# LoraGateway.net
KiCad netlist of a schematic drawn in EAGLE
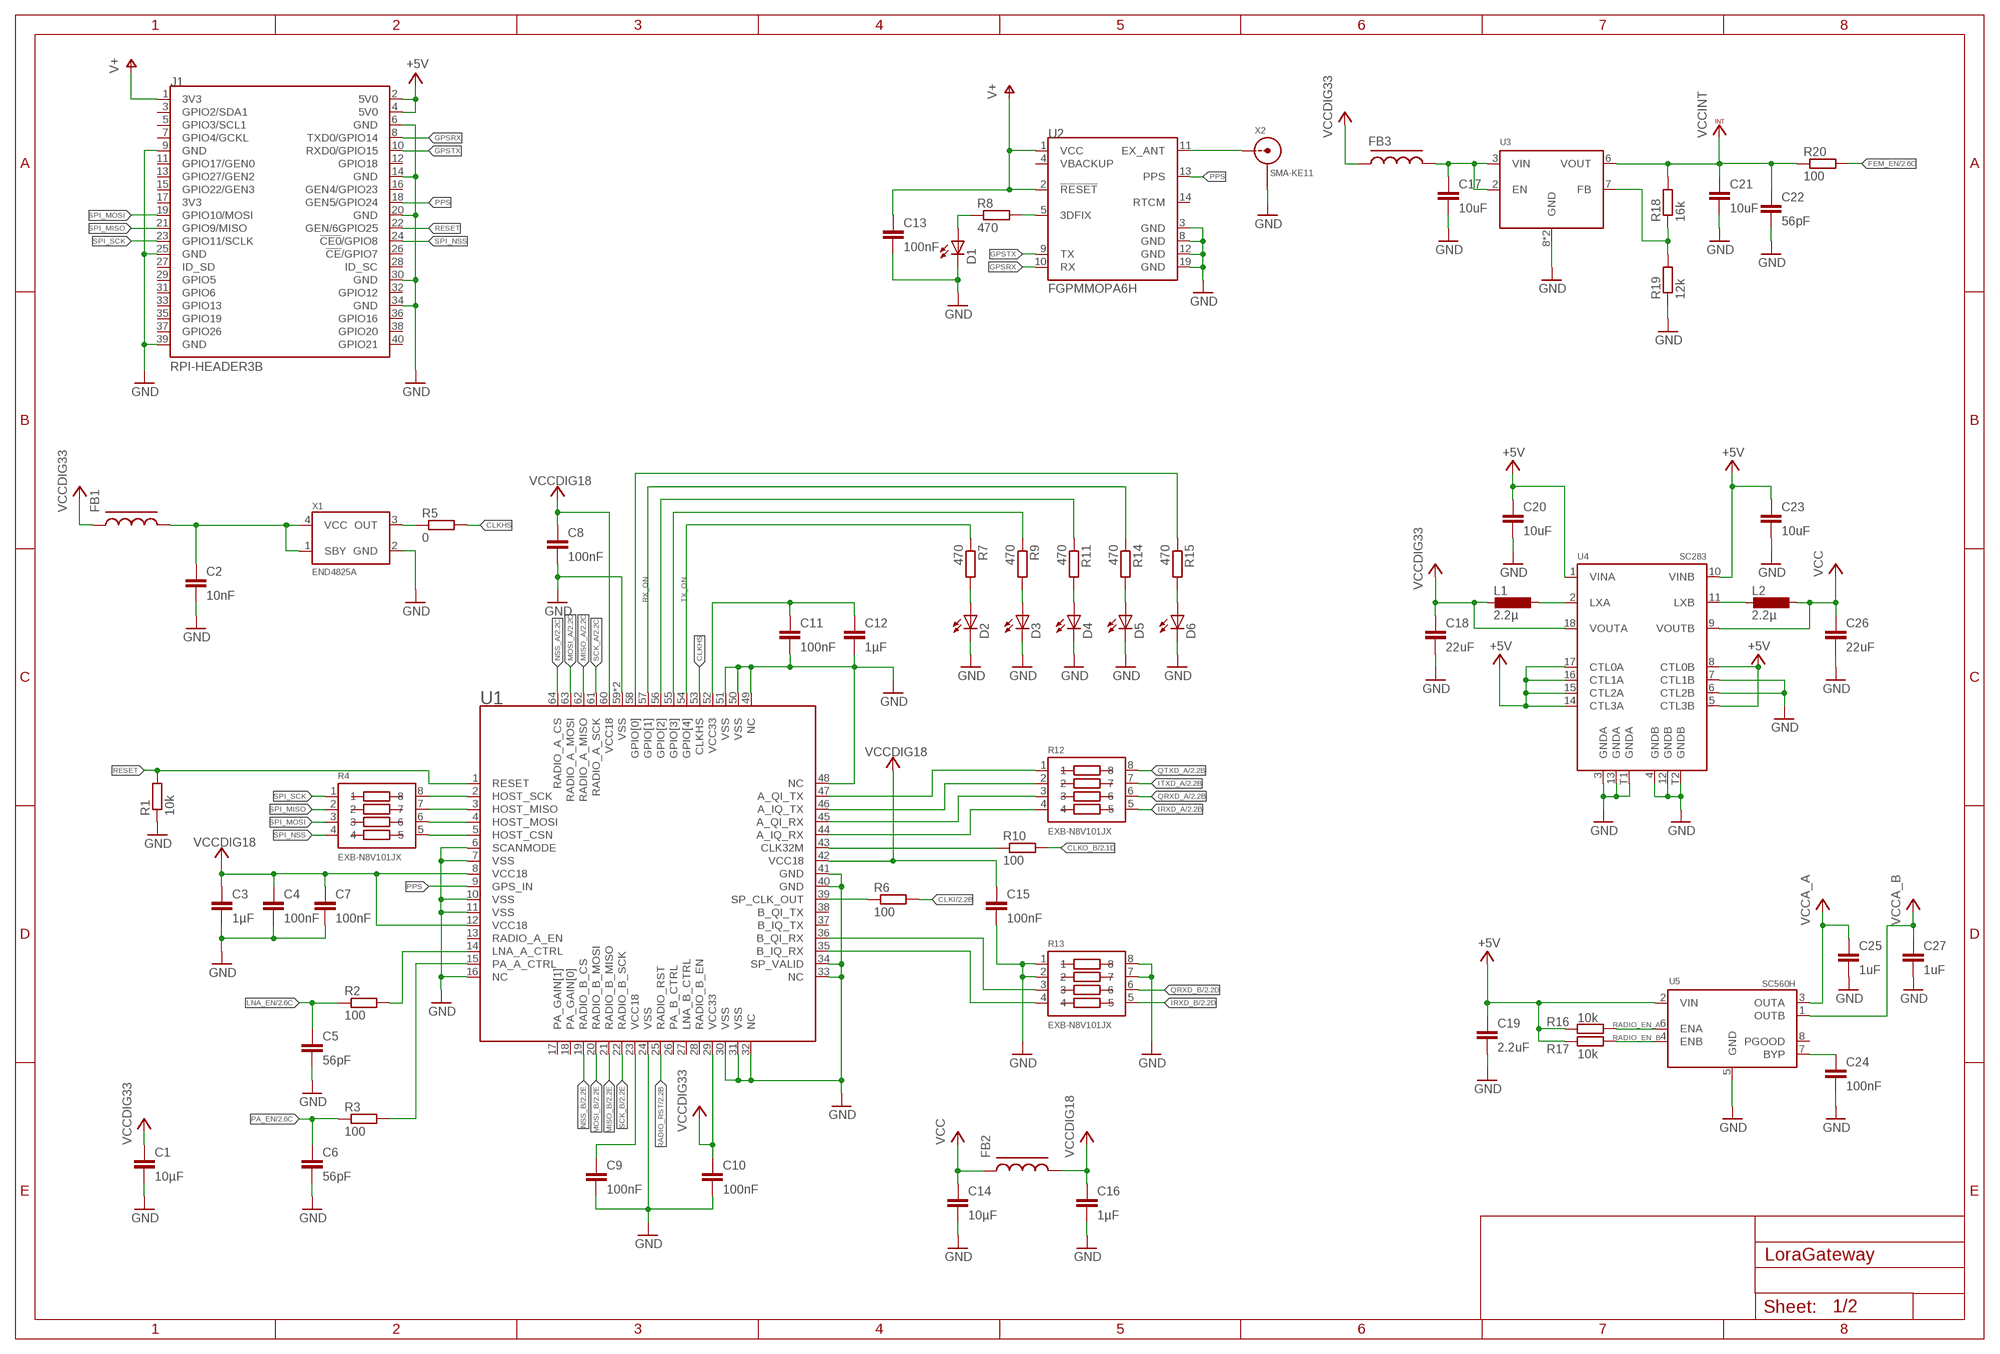
[diagram p0: schematic, sheet 1]
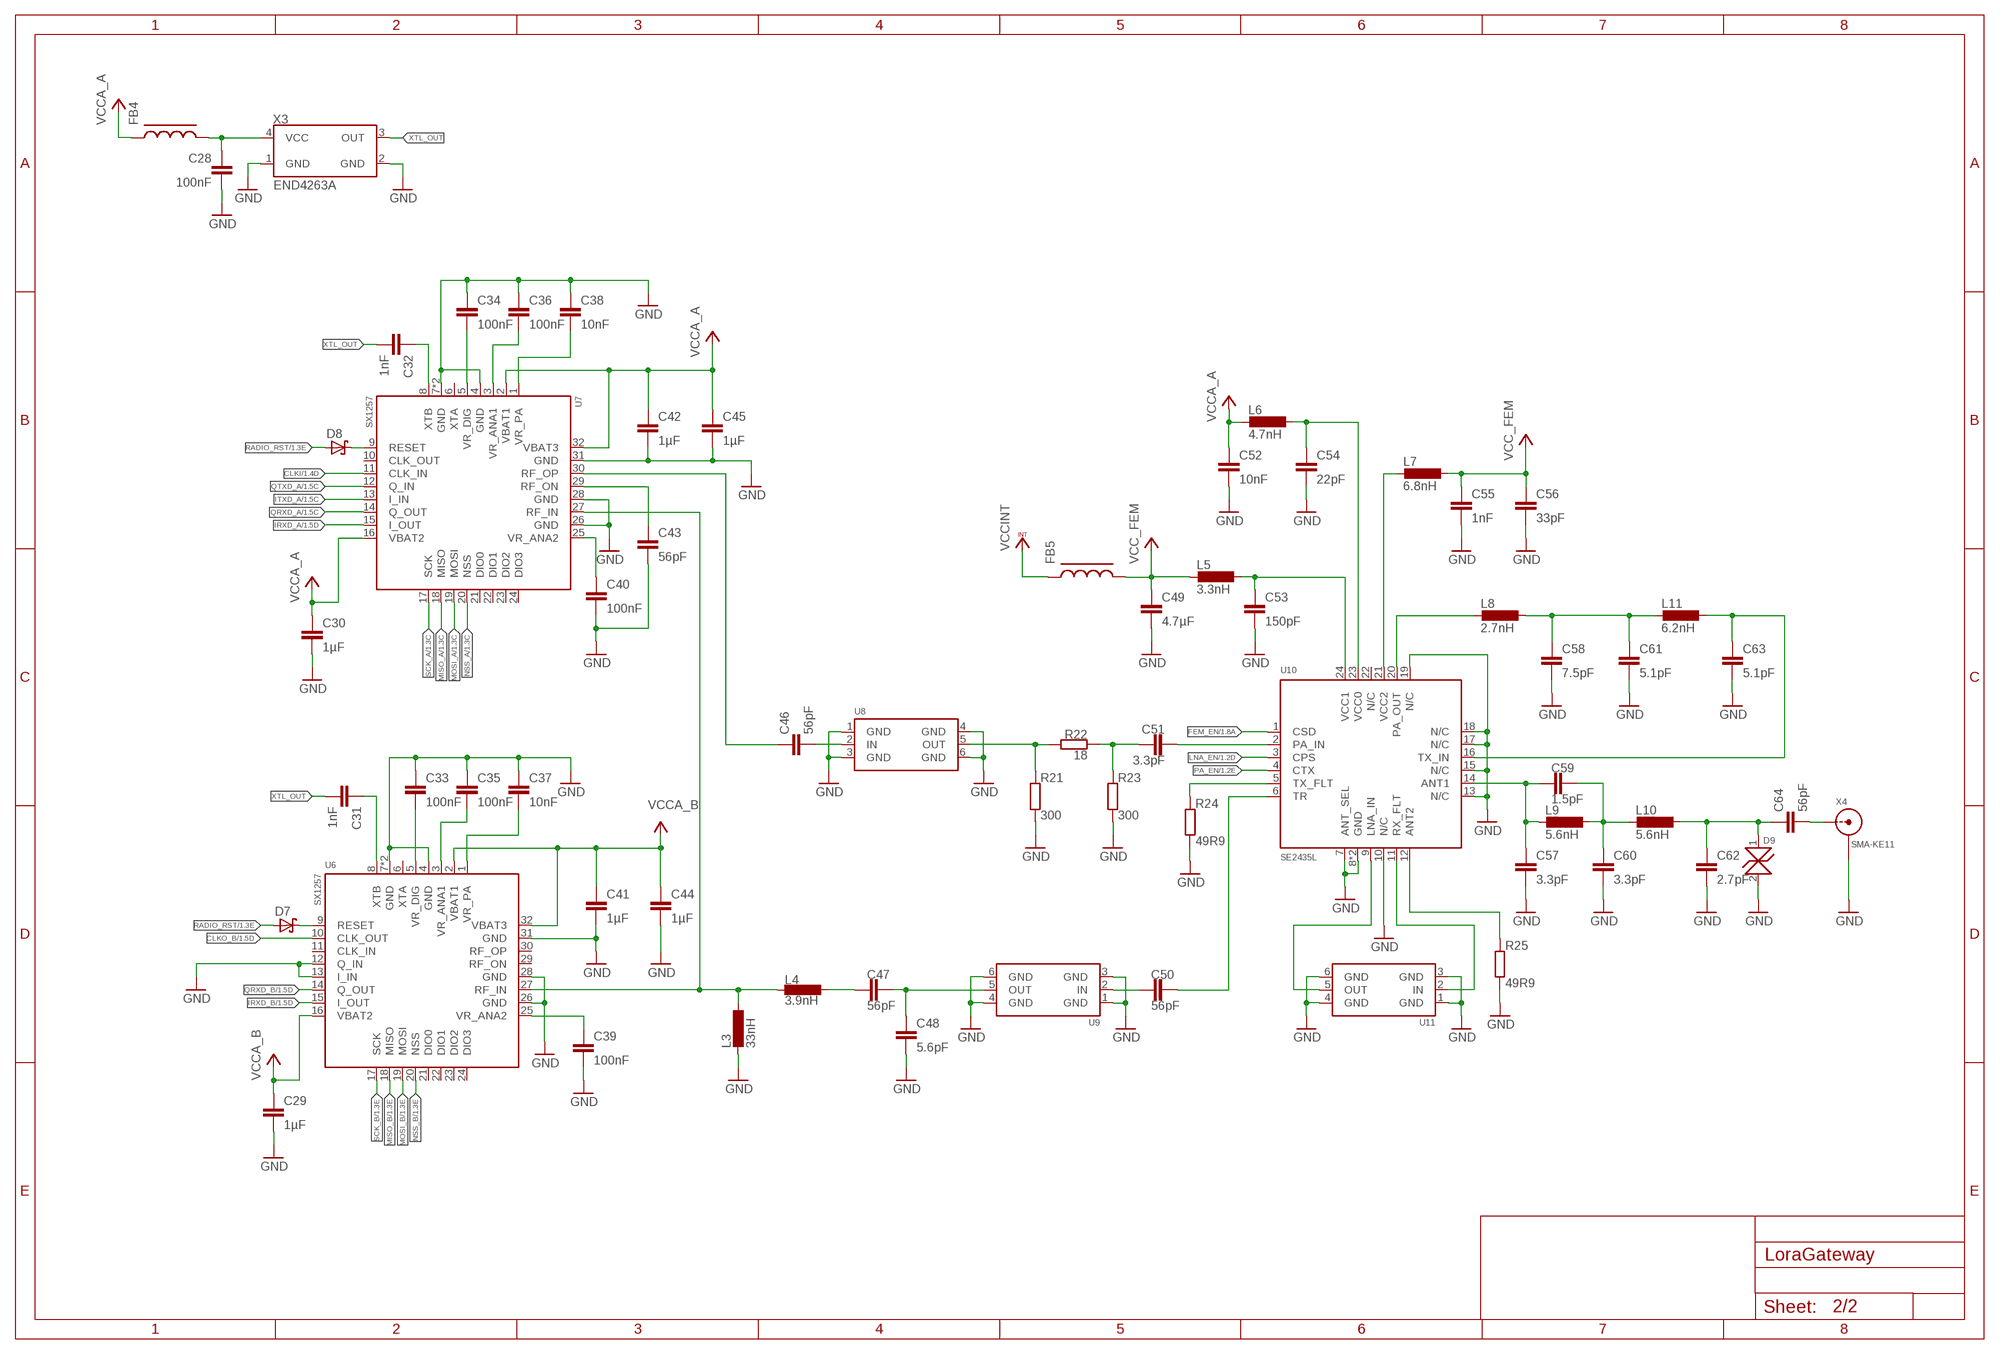
[diagram p1: schematic, sheet 2]

(export (version "E")
  (design (tool "Eeschema 10.0.6"))
  (components
    (comp (ref "C28")
      (value "100nF")
      (footprint "eagle-import:C0402")
      (libsource (lib "eagle-import") (part "C-EU0402"))
    )
    (comp (ref "C29")
      (value "1µF")
      (footprint "eagle-import:C0402")
      (libsource (lib "eagle-import") (part "C-EU0402"))
    )
    (comp (ref "C30")
      (value "1µF")
      (footprint "eagle-import:C0402")
      (libsource (lib "eagle-import") (part "C-EU0402"))
    )
    (comp (ref "C31")
      (value "1nF")
      (footprint "eagle-import:C0402")
      (libsource (lib "eagle-import") (part "C-EU0402"))
    )
    (comp (ref "C32")
      (value "1nF")
      (footprint "eagle-import:C0402")
      (fields (field (name "OC_DIGIKEY") "490-6348-1-ND"))
      (libsource (lib "eagle-import") (part "C-EU0402"))
    )
    (comp (ref "C33")
      (value "100nF")
      (footprint "eagle-import:C0402")
      (libsource (lib "eagle-import") (part "C-EU0402"))
    )
    (comp (ref "C34")
      (value "100nF")
      (footprint "eagle-import:C0402")
      (libsource (lib "eagle-import") (part "C-EU0402"))
    )
    (comp (ref "C35")
      (value "100nF")
      (footprint "eagle-import:C0402")
      (libsource (lib "eagle-import") (part "C-EU0402"))
    )
    (comp (ref "C36")
      (value "100nF")
      (footprint "eagle-import:C0402")
      (libsource (lib "eagle-import") (part "C-EU0402"))
    )
    (comp (ref "C37")
      (value "10nF")
      (footprint "eagle-import:C0402")
      (libsource (lib "eagle-import") (part "C-EU0402"))
    )
    (comp (ref "C38")
      (value "10nF")
      (footprint "eagle-import:C0402")
      (libsource (lib "eagle-import") (part "C-EU0402"))
    )
    (comp (ref "C39")
      (value "100nF")
      (footprint "eagle-import:C0402")
      (libsource (lib "eagle-import") (part "C-EU0402"))
    )
    (comp (ref "C40")
      (value "100nF")
      (footprint "eagle-import:C0402")
      (libsource (lib "eagle-import") (part "C-EU0402"))
    )
    (comp (ref "C41")
      (value "1µF")
      (footprint "eagle-import:C0402")
      (libsource (lib "eagle-import") (part "C-EU0402"))
    )
    (comp (ref "C42")
      (value "1µF")
      (footprint "eagle-import:C0402")
      (libsource (lib "eagle-import") (part "C-EU0402"))
    )
    (comp (ref "C43")
      (value "56pF")
      (footprint "eagle-import:C0402")
      (libsource (lib "eagle-import") (part "C-EU0402"))
    )
    (comp (ref "C44")
      (value "1µF")
      (footprint "eagle-import:C0402")
      (libsource (lib "eagle-import") (part "C-EU0402"))
    )
    (comp (ref "C45")
      (value "1µF")
      (footprint "eagle-import:C0402")
      (libsource (lib "eagle-import") (part "C-EU0402"))
    )
    (comp (ref "C46")
      (value "56pF")
      (footprint "eagle-import:C0402")
      (libsource (lib "eagle-import") (part "C-EU0402"))
    )
    (comp (ref "C47")
      (value "56pF")
      (footprint "eagle-import:C0402")
      (libsource (lib "eagle-import") (part "C-EU0402"))
    )
    (comp (ref "C48")
      (value "5.6pF")
      (footprint "eagle-import:C0402")
      (libsource (lib "eagle-import") (part "C-EU0402"))
    )
    (comp (ref "C49")
      (value "4.7µF")
      (footprint "eagle-import:C0603")
      (libsource (lib "eagle-import") (part "C-EU0603"))
    )
    (comp (ref "C50")
      (value "56pF")
      (footprint "eagle-import:C0402")
      (libsource (lib "eagle-import") (part "C-EU0402"))
    )
    (comp (ref "C51")
      (value "3.3pF")
      (footprint "eagle-import:C0402")
      (libsource (lib "eagle-import") (part "C-EU0402"))
    )
    (comp (ref "C52")
      (value "10nF")
      (footprint "eagle-import:C0402")
      (libsource (lib "eagle-import") (part "C-EU0402"))
    )
    (comp (ref "C53")
      (value "150pF")
      (footprint "eagle-import:C0402")
      (libsource (lib "eagle-import") (part "C-EU0402"))
    )
    (comp (ref "C54")
      (value "22pF")
      (footprint "eagle-import:C0402")
      (libsource (lib "eagle-import") (part "C-EU0402"))
    )
    (comp (ref "C55")
      (value "1nF")
      (footprint "eagle-import:C0402")
      (libsource (lib "eagle-import") (part "C-EU0402"))
    )
    (comp (ref "C56")
      (value "33pF")
      (footprint "eagle-import:C0402")
      (libsource (lib "eagle-import") (part "C-EU0402"))
    )
    (comp (ref "C57")
      (value "3.3pF")
      (footprint "eagle-import:C0402")
      (libsource (lib "eagle-import") (part "C-EU0402"))
    )
    (comp (ref "C58")
      (value "7.5pF")
      (footprint "eagle-import:C0402")
      (libsource (lib "eagle-import") (part "C-EU0402"))
    )
    (comp (ref "C59")
      (value "1.5pF")
      (footprint "eagle-import:C0402")
      (libsource (lib "eagle-import") (part "C-EU0402"))
    )
    (comp (ref "C60")
      (value "3.3pF")
      (footprint "eagle-import:C0402")
      (libsource (lib "eagle-import") (part "C-EU0402"))
    )
    (comp (ref "C61")
      (value "5.1pF")
      (footprint "eagle-import:C0402")
      (libsource (lib "eagle-import") (part "C-EU0402"))
    )
    (comp (ref "C62")
      (value "2.7pF")
      (footprint "eagle-import:C0402")
      (libsource (lib "eagle-import") (part "C-EU0402"))
    )
    (comp (ref "C63")
      (value "5.1pF")
      (footprint "eagle-import:C0402")
      (libsource (lib "eagle-import") (part "C-EU0402"))
    )
    (comp (ref "C64")
      (value "56pF")
      (footprint "eagle-import:C0402")
      (libsource (lib "eagle-import") (part "C-EU0402"))
    )
    (comp (ref "D7")
      (value "BAT54XV2T1G")
      (footprint "eagle-import:SOD523")
      (libsource (lib "eagle-import") (part "BAT54XV2T1G"))
    )
    (comp (ref "D8")
      (value "BAT54XV2T1G")
      (footprint "eagle-import:SOD523")
      (libsource (lib "eagle-import") (part "BAT54XV2T1G"))
    )
    (comp (ref "D9")
      (value "LXES15AAA1-153")
      (footprint "eagle-import:LXES15AAA1-153")
      (libsource (lib "eagle-import") (part "LXES15AAA1-153"))
    )
    (comp (ref "FB4")
      (value "BLM15PG100SN1D0402")
      (footprint "eagle-import:L0402")
      (libsource (lib "eagle-import") (part "BLM15PG100SN1D0402"))
    )
    (comp (ref "FB5")
      (value "BLM18PG121SH1D")
      (footprint "eagle-import:L0603")
      (libsource (lib "eagle-import") (part "BLM18PG121SH1D"))
    )
    (comp (ref "L3")
      (value "33nH")
      (footprint "eagle-import:L0402")
      (libsource (lib "eagle-import") (part "L-EU0402"))
    )
    (comp (ref "L4")
      (value "3.9nH")
      (footprint "eagle-import:L0402")
      (libsource (lib "eagle-import") (part "L-EU0402"))
    )
    (comp (ref "L5")
      (value "3.3nH")
      (footprint "eagle-import:L0402")
      (libsource (lib "eagle-import") (part "L-EU0402"))
    )
    (comp (ref "L6")
      (value "4.7nH")
      (footprint "eagle-import:L0402")
      (libsource (lib "eagle-import") (part "L-EU0402"))
    )
    (comp (ref "L7")
      (value "6.8nH")
      (footprint "eagle-import:L0402")
      (libsource (lib "eagle-import") (part "L-EU0402"))
    )
    (comp (ref "L8")
      (value "2.7nH")
      (footprint "eagle-import:L0402")
      (libsource (lib "eagle-import") (part "L-EU0402"))
    )
    (comp (ref "L9")
      (value "5.6nH")
      (footprint "eagle-import:L0402")
      (libsource (lib "eagle-import") (part "L-EU0402"))
    )
    (comp (ref "L10")
      (value "5.6nH")
      (footprint "eagle-import:L0402")
      (libsource (lib "eagle-import") (part "L-EU0402"))
    )
    (comp (ref "L11")
      (value "6.2nH")
      (footprint "eagle-import:L0402")
      (libsource (lib "eagle-import") (part "L-EU0402"))
    )
    (comp (ref "R21")
      (value "300")
      (footprint "eagle-import:R0402")
      (libsource (lib "eagle-import") (part "R-EU0402"))
    )
    (comp (ref "R22")
      (value "18")
      (footprint "eagle-import:R0402")
      (libsource (lib "eagle-import") (part "R-EU0402"))
    )
    (comp (ref "R23")
      (value "300")
      (footprint "eagle-import:R0402")
      (libsource (lib "eagle-import") (part "R-EU0402"))
    )
    (comp (ref "R24")
      (value "49R9")
      (footprint "eagle-import:R0402")
      (libsource (lib "eagle-import") (part "R-EU0402"))
    )
    (comp (ref "R25")
      (value "49R9")
      (footprint "eagle-import:R0402")
      (libsource (lib "eagle-import") (part "R-EU0402"))
    )
    (comp (ref "U6")
      (value "SX1257")
      (footprint "eagle-import:QFN32")
      (libsource (lib "eagle-import") (part "SX1257"))
    )
    (comp (ref "U7")
      (value "SX1257")
      (footprint "eagle-import:QFN32")
      (libsource (lib "eagle-import") (part "SX1257"))
    )
    (comp (ref "U8")
      (value "B39871B3717U410")
      (footprint "eagle-import:DCC6C-3X3")
      (libsource (lib "eagle-import") (part "B39871B3717U410"))
    )
    (comp (ref "U9")
      (value "B39871B3717U410")
      (footprint "eagle-import:DCC6C-3X3")
      (libsource (lib "eagle-import") (part "B39871B3717U410"))
    )
    (comp (ref "U10")
      (value "SE2435L")
      (footprint "eagle-import:VQFN24-4X4")
      (libsource (lib "eagle-import") (part "SE2435L"))
    )
    (comp (ref "U11")
      (value "B39871B3717U410")
      (footprint "eagle-import:DCC6C-3X3")
      (libsource (lib "eagle-import") (part "B39871B3717U410"))
    )
    (comp (ref "X3")
      (value "END4263A")
      (footprint "eagle-import:2.0X1.6MM")
      (libsource (lib "eagle-import") (part "END4263A"))
    )
    (comp (ref "X4")
      (value "SMA-KE11")
      (footprint "eagle-import:J502-ND-142-0711-871_876")
      (libsource (lib "eagle-import") (part "SMA-KE11"))
    )
    (comp (ref "C1")
      (value "10µF")
      (footprint "eagle-import:C0805")
      (libsource (lib "eagle-import") (part "C-EU0805"))
    )
    (comp (ref "C2")
      (value "10nF")
      (footprint "eagle-import:C0402")
      (libsource (lib "eagle-import") (part "C-EU0402"))
    )
    (comp (ref "C3")
      (value "1µF")
      (footprint "eagle-import:C0402")
      (libsource (lib "eagle-import") (part "C-EU0402"))
    )
    (comp (ref "C4")
      (value "100nF")
      (footprint "eagle-import:C0402")
      (libsource (lib "eagle-import") (part "C-EU0402"))
    )
    (comp (ref "C5")
      (value "56pF")
      (footprint "eagle-import:C0402")
      (libsource (lib "eagle-import") (part "C-EU0402"))
    )
    (comp (ref "C6")
      (value "56pF")
      (footprint "eagle-import:C0402")
      (libsource (lib "eagle-import") (part "C-EU0402"))
    )
    (comp (ref "C7")
      (value "100nF")
      (footprint "eagle-import:C0402")
      (libsource (lib "eagle-import") (part "C-EU0402"))
    )
    (comp (ref "C8")
      (value "100nF")
      (footprint "eagle-import:C0402")
      (libsource (lib "eagle-import") (part "C-EU0402"))
    )
    (comp (ref "C9")
      (value "100nF")
      (footprint "eagle-import:C0402")
      (libsource (lib "eagle-import") (part "C-EU0402"))
    )
    (comp (ref "C10")
      (value "100nF")
      (footprint "eagle-import:C0402")
      (libsource (lib "eagle-import") (part "C-EU0402"))
    )
    (comp (ref "C11")
      (value "100nF")
      (footprint "eagle-import:C0402")
      (libsource (lib "eagle-import") (part "C-EU0402"))
    )
    (comp (ref "C12")
      (value "1µF")
      (footprint "eagle-import:C0402")
      (libsource (lib "eagle-import") (part "C-EU0402"))
    )
    (comp (ref "C13")
      (value "100nF")
      (footprint "eagle-import:C0402")
      (libsource (lib "eagle-import") (part "C-EU0402"))
    )
    (comp (ref "C14")
      (value "10µF")
      (footprint "eagle-import:C0805")
      (libsource (lib "eagle-import") (part "C-EU0805"))
    )
    (comp (ref "C15")
      (value "100nF")
      (footprint "eagle-import:C0402")
      (libsource (lib "eagle-import") (part "C-EU0402"))
    )
    (comp (ref "C16")
      (value "1µF")
      (footprint "eagle-import:C0603")
      (libsource (lib "eagle-import") (part "C-EU0603"))
    )
    (comp (ref "C17")
      (value "10uF")
      (footprint "eagle-import:C0805")
      (libsource (lib "eagle-import") (part "C-EU0805"))
    )
    (comp (ref "C18")
      (value "22uF")
      (footprint "eagle-import:C1206")
      (libsource (lib "eagle-import") (part "C-EU1206"))
    )
    (comp (ref "C19")
      (value "2.2uF")
      (footprint "eagle-import:C0603")
      (libsource (lib "eagle-import") (part "C-EU0603"))
    )
    (comp (ref "C20")
      (value "10uF")
      (footprint "eagle-import:C1206")
      (libsource (lib "eagle-import") (part "C-EU1206"))
    )
    (comp (ref "C21")
      (value "10uF")
      (footprint "eagle-import:C0805")
      (libsource (lib "eagle-import") (part "C-EU0805"))
    )
    (comp (ref "C22")
      (value "56pF")
      (footprint "eagle-import:C0402")
      (libsource (lib "eagle-import") (part "C-EU0402"))
    )
    (comp (ref "C23")
      (value "10uF")
      (footprint "eagle-import:C1206")
      (libsource (lib "eagle-import") (part "C-EU1206"))
    )
    (comp (ref "C24")
      (value "100nF")
      (footprint "eagle-import:C0402")
      (libsource (lib "eagle-import") (part "C-EUC0402"))
    )
    (comp (ref "C25")
      (value "1uF")
      (footprint "eagle-import:C0805")
      (libsource (lib "eagle-import") (part "C-EU0805"))
    )
    (comp (ref "C26")
      (value "22uF")
      (footprint "eagle-import:C1206")
      (libsource (lib "eagle-import") (part "C-EU1206"))
    )
    (comp (ref "C27")
      (value "1uF")
      (footprint "eagle-import:C0805")
      (libsource (lib "eagle-import") (part "C-EU0805"))
    )
    (comp (ref "D1")
      (value "LED")
      (footprint "eagle-import:D0603")
      (libsource (lib "eagle-import") (part "LED"))
    )
    (comp (ref "D2")
      (value "LED")
      (footprint "eagle-import:D0603")
      (libsource (lib "eagle-import") (part "LED"))
    )
    (comp (ref "D3")
      (value "LED")
      (footprint "eagle-import:D0603")
      (libsource (lib "eagle-import") (part "LED"))
    )
    (comp (ref "D4")
      (value "LED")
      (footprint "eagle-import:D0603")
      (libsource (lib "eagle-import") (part "LED"))
    )
    (comp (ref "D5")
      (value "LED")
      (footprint "eagle-import:D0603")
      (libsource (lib "eagle-import") (part "LED"))
    )
    (comp (ref "D6")
      (value "LED")
      (footprint "eagle-import:D0603")
      (libsource (lib "eagle-import") (part "LED"))
    )
    (comp (ref "FB1")
      (value "BLM15PG100SN1D0402")
      (footprint "eagle-import:L0402")
      (libsource (lib "eagle-import") (part "BLM15PG100SN1D0402"))
    )
    (comp (ref "FB2")
      (value "BLM15PG100SN1D0402")
      (footprint "eagle-import:L0402")
      (libsource (lib "eagle-import") (part "BLM15PG100SN1D0402"))
    )
    (comp (ref "FB3")
      (value "BLM15PG100SN1D0402")
      (footprint "eagle-import:L0402")
      (libsource (lib "eagle-import") (part "BLM15PG100SN1D0402"))
    )
    (comp (ref "J1")
      (value "RPI-HEADER3B")
      (footprint "eagle-import:RPI")
      (libsource (lib "eagle-import") (part "RPI-HEADER3B"))
    )
    (comp (ref "L1")
      (value "2.2µ")
      (footprint "eagle-import:ASPI-0418")
      (libsource (lib "eagle-import") (part "ASPI-0418"))
    )
    (comp (ref "L2")
      (value "2.2µ")
      (footprint "eagle-import:ASPI-0418")
      (libsource (lib "eagle-import") (part "ASPI-0418"))
    )
    (comp (ref "R1")
      (value "10k")
      (footprint "eagle-import:R0402")
      (libsource (lib "eagle-import") (part "R-EU_R0402"))
    )
    (comp (ref "R2")
      (value "100")
      (footprint "eagle-import:R0402")
      (libsource (lib "eagle-import") (part "R-EU0402"))
    )
    (comp (ref "R3")
      (value "100")
      (footprint "eagle-import:R0402")
      (libsource (lib "eagle-import") (part "R-EU0402"))
    )
    (comp (ref "R4")
      (value "EXB-N8V101JX")
      (footprint "eagle-import:EXB28V")
      (libsource (lib "eagle-import") (part "EXB-N8V101JX"))
    )
    (comp (ref "R5")
      (value "0")
      (footprint "eagle-import:R0402")
      (libsource (lib "eagle-import") (part "R-EU0402"))
    )
    (comp (ref "R6")
      (value "100")
      (footprint "eagle-import:R0402")
      (libsource (lib "eagle-import") (part "R-EU0402"))
    )
    (comp (ref "R7")
      (value "470")
      (footprint "eagle-import:R0603")
      (libsource (lib "eagle-import") (part "R-EU0603"))
    )
    (comp (ref "R8")
      (value "470")
      (footprint "eagle-import:R0402")
      (libsource (lib "eagle-import") (part "R-EU_R0402"))
    )
    (comp (ref "R9")
      (value "470")
      (footprint "eagle-import:R0603")
      (libsource (lib "eagle-import") (part "R-EU0603"))
    )
    (comp (ref "R10")
      (value "100")
      (footprint "eagle-import:R0402")
      (libsource (lib "eagle-import") (part "R-EU0402"))
    )
    (comp (ref "R11")
      (value "470")
      (footprint "eagle-import:R0603")
      (libsource (lib "eagle-import") (part "R-EU0603"))
    )
    (comp (ref "R12")
      (value "EXB-N8V101JX")
      (footprint "eagle-import:EXB28V")
      (libsource (lib "eagle-import") (part "EXB-N8V101JX"))
    )
    (comp (ref "R13")
      (value "EXB-N8V101JX")
      (footprint "eagle-import:EXB28V")
      (libsource (lib "eagle-import") (part "EXB-N8V101JX"))
    )
    (comp (ref "R14")
      (value "470")
      (footprint "eagle-import:R0603")
      (libsource (lib "eagle-import") (part "R-EU0603"))
    )
    (comp (ref "R15")
      (value "470")
      (footprint "eagle-import:R0603")
      (libsource (lib "eagle-import") (part "R-EU0603"))
    )
    (comp (ref "R16")
      (value "10k")
      (footprint "eagle-import:R0402")
      (libsource (lib "eagle-import") (part "R-EU0402"))
    )
    (comp (ref "R17")
      (value "10k")
      (footprint "eagle-import:R0402")
      (libsource (lib "eagle-import") (part "R-EU0402"))
    )
    (comp (ref "R18")
      (value "16k")
      (footprint "eagle-import:R0402")
      (libsource (lib "eagle-import") (part "R-EU0402"))
    )
    (comp (ref "R19")
      (value "12k")
      (footprint "eagle-import:R0402")
      (libsource (lib "eagle-import") (part "R-EU0402"))
    )
    (comp (ref "R20")
      (value "100")
      (footprint "eagle-import:R0402")
      (libsource (lib "eagle-import") (part "R-EU0402"))
    )
    (comp (ref "U1")
      (value "SX1308")
      (footprint "eagle-import:QFN64-9X9")
      (libsource (lib "eagle-import") (part "SX1308"))
    )
    (comp (ref "U2")
      (value "FGPMMOPA6H")
      (footprint "eagle-import:FGPMMOPA6H")
      (libsource (lib "eagle-import") (part "FGPMMOPA6H"))
    )
    (comp (ref "U3")
      (value "SC4212")
      (footprint "eagle-import:3X3MLPD-8")
      (libsource (lib "eagle-import") (part "SC4212"))
    )
    (comp (ref "U4")
      (value "SC283")
      (footprint "eagle-import:2X3MLPQ-W18")
      (libsource (lib "eagle-import") (part "SC283"))
    )
    (comp (ref "U5")
      (value "SC560H")
      (footprint "eagle-import:MLPQ-UT8")
      (libsource (lib "eagle-import") (part "SC560H"))
    )
    (comp (ref "X1")
      (value "END4825A")
      (footprint "eagle-import:2.5X2.0MM")
      (libsource (lib "eagle-import") (part "END4825A"))
    )
    (comp (ref "X2")
      (value "SMA-KE11")
      (footprint "eagle-import:J502-ND-142-0711-871_876")
      (libsource (lib "eagle-import") (part "SMA-KE11"))
    )
  )
  (nets
    (net (code "1") (name "+5V") (class "Default")
      (node (ref "C19") (pin "1") (pinfunction "1_1") (pintype "passive"))
      (node (ref "C20") (pin "1") (pinfunction "1_1") (pintype "passive"))
      (node (ref "C23") (pin "1") (pinfunction "1_1") (pintype "passive"))
      (node (ref "J1") (pin "2") (pinfunction "5V0_2") (pintype "power_in"))
      (node (ref "J1") (pin "4") (pinfunction "5V0_4") (pintype "power_in"))
      (node (ref "R16") (pin "1") (pinfunction "1_1") (pintype "passive"))
      (node (ref "R17") (pin "1") (pinfunction "1_1") (pintype "passive"))
      (node (ref "U4") (pin "1") (pinfunction "VINA_1") (pintype "bidirectional"))
      (node (ref "U4") (pin "10") (pinfunction "VINB_10") (pintype "bidirectional"))
      (node (ref "U4") (pin "14") (pinfunction "CTL3A_14") (pintype "bidirectional"))
      (node (ref "U4") (pin "15") (pinfunction "CTL2A_15") (pintype "bidirectional"))
      (node (ref "U4") (pin "16") (pinfunction "CTL1A_16") (pintype "bidirectional"))
      (node (ref "U4") (pin "17") (pinfunction "CTL0A_17") (pintype "bidirectional"))
      (node (ref "U4") (pin "5") (pinfunction "CTL3B_5") (pintype "bidirectional"))
      (node (ref "U4") (pin "8") (pinfunction "CTL0B_8") (pintype "bidirectional"))
      (node (ref "U5") (pin "2") (pinfunction "VIN_2") (pintype "bidirectional"))
    )
    (net (code "2") (name "3V3") (class "Default")
      (node (ref "J1") (pin "17") (pinfunction "3V3_17") (pintype "power_in"))
    )
    (net (code "3") (name "CLKHS") (class "Default")
      (node (ref "R5") (pin "2") (pinfunction "2_2") (pintype "passive"))
      (node (ref "U1") (pin "53") (pinfunction "CLKHS_53") (pintype "bidirectional"))
    )
    (net (code "4") (name "CLKI") (class "Default")
      (node (ref "R6") (pin "2") (pinfunction "2_2") (pintype "passive"))
      (node (ref "U7") (pin "11") (pinfunction "CLK_IN_11") (pintype "bidirectional"))
    )
    (net (code "5") (name "CLKO_B") (class "Default")
      (node (ref "R10") (pin "2") (pinfunction "2_2") (pintype "passive"))
      (node (ref "U6") (pin "10") (pinfunction "CLK_OUT_10") (pintype "bidirectional"))
    )
    (net (code "6") (name "FEM_EN") (class "Default")
      (node (ref "R20") (pin "2") (pinfunction "2_2") (pintype "passive"))
      (node (ref "U10") (pin "1") (pinfunction "CSD_1") (pintype "bidirectional"))
    )
    (net (code "7") (name "GND") (class "Default")
      (node (ref "C1") (pin "2") (pinfunction "2_2") (pintype "passive"))
      (node (ref "C10") (pin "2") (pinfunction "2_2") (pintype "passive"))
      (node (ref "C11") (pin "2") (pinfunction "2_2") (pintype "passive"))
      (node (ref "C12") (pin "2") (pinfunction "2_2") (pintype "passive"))
      (node (ref "C13") (pin "2") (pinfunction "2_2") (pintype "passive"))
      (node (ref "C14") (pin "2") (pinfunction "2_2") (pintype "passive"))
      (node (ref "C15") (pin "2") (pinfunction "2_2") (pintype "passive"))
      (node (ref "C16") (pin "2") (pinfunction "2_2") (pintype "passive"))
      (node (ref "C17") (pin "2") (pinfunction "2_2") (pintype "passive"))
      (node (ref "C18") (pin "2") (pinfunction "2_2") (pintype "passive"))
      (node (ref "C19") (pin "2") (pinfunction "2_2") (pintype "passive"))
      (node (ref "C2") (pin "2") (pinfunction "2_2") (pintype "passive"))
      (node (ref "C20") (pin "2") (pinfunction "2_2") (pintype "passive"))
      (node (ref "C21") (pin "2") (pinfunction "2_2") (pintype "passive"))
      (node (ref "C22") (pin "2") (pinfunction "2_2") (pintype "passive"))
      (node (ref "C23") (pin "2") (pinfunction "2_2") (pintype "passive"))
      (node (ref "C24") (pin "2") (pinfunction "2_2") (pintype "passive"))
      (node (ref "C25") (pin "2") (pinfunction "2_2") (pintype "passive"))
      (node (ref "C26") (pin "2") (pinfunction "2_2") (pintype "passive"))
      (node (ref "C27") (pin "2") (pinfunction "2_2") (pintype "passive"))
      (node (ref "C28") (pin "2") (pinfunction "2_2") (pintype "passive"))
      (node (ref "C29") (pin "2") (pinfunction "2_2") (pintype "passive"))
      (node (ref "C3") (pin "2") (pinfunction "2_2") (pintype "passive"))
      (node (ref "C30") (pin "2") (pinfunction "2_2") (pintype "passive"))
      (node (ref "C33") (pin "1") (pinfunction "1_1") (pintype "passive"))
      (node (ref "C34") (pin "1") (pinfunction "1_1") (pintype "passive"))
      (node (ref "C35") (pin "1") (pinfunction "1_1") (pintype "passive"))
      (node (ref "C36") (pin "1") (pinfunction "1_1") (pintype "passive"))
      (node (ref "C37") (pin "1") (pinfunction "1_1") (pintype "passive"))
      (node (ref "C38") (pin "1") (pinfunction "1_1") (pintype "passive"))
      (node (ref "C39") (pin "2") (pinfunction "2_2") (pintype "passive"))
      (node (ref "C4") (pin "2") (pinfunction "2_2") (pintype "passive"))
      (node (ref "C40") (pin "2") (pinfunction "2_2") (pintype "passive"))
      (node (ref "C41") (pin "2") (pinfunction "2_2") (pintype "passive"))
      (node (ref "C42") (pin "2") (pinfunction "2_2") (pintype "passive"))
      (node (ref "C43") (pin "2") (pinfunction "2_2") (pintype "passive"))
      (node (ref "C44") (pin "2") (pinfunction "2_2") (pintype "passive"))
      (node (ref "C45") (pin "2") (pinfunction "2_2") (pintype "passive"))
      (node (ref "C48") (pin "2") (pinfunction "2_2") (pintype "passive"))
      (node (ref "C49") (pin "2") (pinfunction "2_2") (pintype "passive"))
      (node (ref "C5") (pin "2") (pinfunction "2_2") (pintype "passive"))
      (node (ref "C52") (pin "2") (pinfunction "2_2") (pintype "passive"))
      (node (ref "C53") (pin "2") (pinfunction "2_2") (pintype "passive"))
      (node (ref "C54") (pin "2") (pinfunction "2_2") (pintype "passive"))
      (node (ref "C55") (pin "2") (pinfunction "2_2") (pintype "passive"))
      (node (ref "C56") (pin "2") (pinfunction "2_2") (pintype "passive"))
      (node (ref "C57") (pin "2") (pinfunction "2_2") (pintype "passive"))
      (node (ref "C58") (pin "2") (pinfunction "2_2") (pintype "passive"))
      (node (ref "C6") (pin "2") (pinfunction "2_2") (pintype "passive"))
      (node (ref "C60") (pin "2") (pinfunction "2_2") (pintype "passive"))
      (node (ref "C61") (pin "2") (pinfunction "2_2") (pintype "passive"))
      (node (ref "C62") (pin "2") (pinfunction "2_2") (pintype "passive"))
      (node (ref "C63") (pin "2") (pinfunction "2_2") (pintype "passive"))
      (node (ref "C7") (pin "2") (pinfunction "2_2") (pintype "passive"))
      (node (ref "C8") (pin "2") (pinfunction "2_2") (pintype "passive"))
      (node (ref "C9") (pin "2") (pinfunction "2_2") (pintype "passive"))
      (node (ref "D1") (pin "C") (pinfunction "C_C") (pintype "passive"))
      (node (ref "D2") (pin "C") (pinfunction "C_C") (pintype "passive"))
      (node (ref "D3") (pin "C") (pinfunction "C_C") (pintype "passive"))
      (node (ref "D4") (pin "C") (pinfunction "C_C") (pintype "passive"))
      (node (ref "D5") (pin "C") (pinfunction "C_C") (pintype "passive"))
      (node (ref "D6") (pin "C") (pinfunction "C_C") (pintype "passive"))
      (node (ref "D9") (pin "2") (pinfunction "2_2") (pintype "bidirectional"))
      (node (ref "J1") (pin "14") (pinfunction "GND_14") (pintype "power_in"))
      (node (ref "J1") (pin "20") (pinfunction "GND_20") (pintype "power_in"))
      (node (ref "J1") (pin "25") (pinfunction "GND_25") (pintype "power_in"))
      (node (ref "J1") (pin "30") (pinfunction "GND_30") (pintype "power_in"))
      (node (ref "J1") (pin "34") (pinfunction "GND_34") (pintype "power_in"))
      (node (ref "J1") (pin "39") (pinfunction "GND_39") (pintype "power_in"))
      (node (ref "J1") (pin "6") (pinfunction "GND_6") (pintype "power_in"))
      (node (ref "J1") (pin "9") (pinfunction "GND_9") (pintype "power_in"))
      (node (ref "L3") (pin "2") (pinfunction "2_2") (pintype "passive"))
      (node (ref "R1") (pin "1") (pinfunction "1_1") (pintype "passive"))
      (node (ref "R13") (pin "1") (pinfunction "1_1") (pintype "bidirectional"))
      (node (ref "R13") (pin "2") (pinfunction "2_2") (pintype "bidirectional"))
      (node (ref "R13") (pin "7") (pinfunction "7_7") (pintype "bidirectional"))
      (node (ref "R13") (pin "8") (pinfunction "8_8") (pintype "bidirectional"))
      (node (ref "R19") (pin "1") (pinfunction "1_1") (pintype "passive"))
      (node (ref "R21") (pin "2") (pinfunction "2_2") (pintype "passive"))
      (node (ref "R23") (pin "2") (pinfunction "2_2") (pintype "passive"))
      (node (ref "R24") (pin "1") (pinfunction "1_1") (pintype "passive"))
      (node (ref "R25") (pin "1") (pinfunction "1_1") (pintype "passive"))
      (node (ref "U1") (pin "10") (pinfunction "VSS_10") (pintype "bidirectional"))
      (node (ref "U1") (pin "11") (pinfunction "VSS_11") (pintype "bidirectional"))
      (node (ref "U1") (pin "16") (pinfunction "NC_16") (pintype "bidirectional"))
      (node (ref "U1") (pin "24") (pinfunction "VSS_24") (pintype "bidirectional"))
      (node (ref "U1") (pin "30") (pinfunction "VSS_30") (pintype "bidirectional"))
      (node (ref "U1") (pin "31") (pinfunction "VSS_31") (pintype "bidirectional"))
      (node (ref "U1") (pin "32") (pinfunction "NC_32") (pintype "bidirectional"))
      (node (ref "U1") (pin "33") (pinfunction "NC_33") (pintype "bidirectional"))
      (node (ref "U1") (pin "34") (pinfunction "SP_VALID_34") (pintype "bidirectional"))
      (node (ref "U1") (pin "40") (pinfunction "GND_40") (pintype "bidirectional"))
      (node (ref "U1") (pin "41") (pinfunction "GND_41") (pintype "bidirectional"))
      (node (ref "U1") (pin "48") (pinfunction "NC_48") (pintype "bidirectional"))
      (node (ref "U1") (pin "49") (pinfunction "NC_49") (pintype "bidirectional"))
      (node (ref "U1") (pin "50") (pinfunction "VSS_50") (pintype "bidirectional"))
      (node (ref "U1") (pin "51") (pinfunction "VSS_51") (pintype "bidirectional"))
      (node (ref "U1") (pin "59") (pinfunction "VSS_59") (pintype "bidirectional"))
      (node (ref "U1") (pin "6") (pinfunction "SCANMODE_6") (pintype "bidirectional"))
      (node (ref "U1") (pin "7") (pinfunction "VSS_7") (pintype "bidirectional"))
      (node (ref "U1") (pin "EXP") (pinfunction "VSS_EXP") (pintype "bidirectional"))
      (node (ref "U10") (pin "10") (pinfunction "N/C_10") (pintype "bidirectional"))
      (node (ref "U10") (pin "13") (pinfunction "N/C_13") (pintype "bidirectional"))
      (node (ref "U10") (pin "15") (pinfunction "N/C_15") (pintype "bidirectional"))
      (node (ref "U10") (pin "17") (pinfunction "N/C_17") (pintype "bidirectional"))
      (node (ref "U10") (pin "18") (pinfunction "N/C_18") (pintype "bidirectional"))
      (node (ref "U10") (pin "19") (pinfunction "N/C_19") (pintype "bidirectional"))
      (node (ref "U10") (pin "7") (pinfunction "ANT_SEL_7") (pintype "bidirectional"))
      (node (ref "U10") (pin "8") (pinfunction "GND_8") (pintype "bidirectional"))
      (node (ref "U10") (pin "GND") (pinfunction "GND_GND") (pintype "bidirectional"))
      (node (ref "U11") (pin "1") (pinfunction "GND_1") (pintype "bidirectional"))
      (node (ref "U11") (pin "3") (pinfunction "GND_3") (pintype "bidirectional"))
      (node (ref "U11") (pin "4") (pinfunction "GND_4") (pintype "bidirectional"))
      (node (ref "U11") (pin "6") (pinfunction "GND_6") (pintype "bidirectional"))
      (node (ref "U2") (pin "12") (pinfunction "GND_12") (pintype "bidirectional"))
      (node (ref "U2") (pin "19") (pinfunction "GND_19") (pintype "bidirectional"))
      (node (ref "U2") (pin "3") (pinfunction "GND_3") (pintype "bidirectional"))
      (node (ref "U2") (pin "8") (pinfunction "GND_8") (pintype "bidirectional"))
      (node (ref "U3") (pin "8") (pinfunction "GND_8") (pintype "bidirectional"))
      (node (ref "U3") (pin "GND") (pinfunction "GND_GND") (pintype "bidirectional"))
      (node (ref "U4") (pin "12") (pinfunction "GNDB_12") (pintype "bidirectional"))
      (node (ref "U4") (pin "13") (pinfunction "GNDA_13") (pintype "bidirectional"))
      (node (ref "U4") (pin "3") (pinfunction "GNDA_3") (pintype "bidirectional"))
      (node (ref "U4") (pin "4") (pinfunction "GNDB_4") (pintype "bidirectional"))
      (node (ref "U4") (pin "6") (pinfunction "CTL2B_6") (pintype "bidirectional"))
      (node (ref "U4") (pin "7") (pinfunction "CTL1B_7") (pintype "bidirectional"))
      (node (ref "U4") (pin "T1") (pinfunction "GNDA_T1") (pintype "bidirectional"))
      (node (ref "U4") (pin "T2") (pinfunction "GNDB_T2") (pintype "bidirectional"))
      (node (ref "U5") (pin "5") (pinfunction "GND_5") (pintype "bidirectional"))
      (node (ref "U6") (pin "12") (pinfunction "Q_IN_12") (pintype "bidirectional"))
      (node (ref "U6") (pin "13") (pinfunction "I_IN_13") (pintype "bidirectional"))
      (node (ref "U6") (pin "26") (pinfunction "GND_26") (pintype "bidirectional"))
      (node (ref "U6") (pin "28") (pinfunction "GND_28") (pintype "bidirectional"))
      (node (ref "U6") (pin "31") (pinfunction "GND_31") (pintype "bidirectional"))
      (node (ref "U6") (pin "4") (pinfunction "GND_4") (pintype "bidirectional"))
      (node (ref "U6") (pin "7") (pinfunction "GND_7") (pintype "bidirectional"))
      (node (ref "U6") (pin "EXP") (pinfunction "GND_EXP") (pintype "bidirectional"))
      (node (ref "U7") (pin "26") (pinfunction "GND_26") (pintype "bidirectional"))
      (node (ref "U7") (pin "28") (pinfunction "GND_28") (pintype "bidirectional"))
      (node (ref "U7") (pin "31") (pinfunction "GND_31") (pintype "bidirectional"))
      (node (ref "U7") (pin "4") (pinfunction "GND_4") (pintype "bidirectional"))
      (node (ref "U7") (pin "7") (pinfunction "GND_7") (pintype "bidirectional"))
      (node (ref "U7") (pin "EXP") (pinfunction "GND_EXP") (pintype "bidirectional"))
      (node (ref "U8") (pin "1") (pinfunction "GND_1") (pintype "bidirectional"))
      (node (ref "U8") (pin "3") (pinfunction "GND_3") (pintype "bidirectional"))
      (node (ref "U8") (pin "4") (pinfunction "GND_4") (pintype "bidirectional"))
      (node (ref "U8") (pin "6") (pinfunction "GND_6") (pintype "bidirectional"))
      (node (ref "U9") (pin "1") (pinfunction "GND_1") (pintype "bidirectional"))
      (node (ref "U9") (pin "3") (pinfunction "GND_3") (pintype "bidirectional"))
      (node (ref "U9") (pin "4") (pinfunction "GND_4") (pintype "bidirectional"))
      (node (ref "U9") (pin "6") (pinfunction "GND_6") (pintype "bidirectional"))
      (node (ref "X1") (pin "2") (pinfunction "GND_2") (pintype "bidirectional"))
      (node (ref "X2") (pin "G@1") (pinfunction "GND_G@1") (pintype "bidirectional"))
      (node (ref "X2") (pin "G@2") (pinfunction "GND_G@2") (pintype "bidirectional"))
      (node (ref "X2") (pin "G@3") (pinfunction "GND_G@3") (pintype "bidirectional"))
      (node (ref "X2") (pin "G@4") (pinfunction "GND_G@4") (pintype "bidirectional"))
      (node (ref "X3") (pin "1") (pinfunction "GND_1") (pintype "bidirectional"))
      (node (ref "X3") (pin "2") (pinfunction "GND_2") (pintype "bidirectional"))
      (node (ref "X4") (pin "G@1") (pinfunction "GND_G@1") (pintype "bidirectional"))
      (node (ref "X4") (pin "G@2") (pinfunction "GND_G@2") (pintype "bidirectional"))
      (node (ref "X4") (pin "G@3") (pinfunction "GND_G@3") (pintype "bidirectional"))
      (node (ref "X4") (pin "G@4") (pinfunction "GND_G@4") (pintype "bidirectional"))
    )
    (net (code "8") (name "GPSRX") (class "Default")
      (node (ref "J1") (pin "8") (pinfunction "TXD0/GPIO14_8") (pintype "bidirectional"))
      (node (ref "U2") (pin "10") (pinfunction "RX_10") (pintype "bidirectional"))
    )
    (net (code "9") (name "GPSTX") (class "Default")
      (node (ref "J1") (pin "10") (pinfunction "RXD0/GPIO15_10") (pintype "bidirectional"))
      (node (ref "U2") (pin "9") (pinfunction "TX_9") (pintype "bidirectional"))
    )
    (net (code "10") (name "IRXD_A") (class "Default")
      (node (ref "R12") (pin "5") (pinfunction "5_5") (pintype "bidirectional"))
      (node (ref "U7") (pin "15") (pinfunction "I_OUT_15") (pintype "bidirectional"))
    )
    (net (code "11") (name "IRXD_B") (class "Default")
      (node (ref "R13") (pin "5") (pinfunction "5_5") (pintype "bidirectional"))
      (node (ref "U6") (pin "15") (pinfunction "I_OUT_15") (pintype "bidirectional"))
    )
    (net (code "12") (name "ITXD_A") (class "Default")
      (node (ref "R12") (pin "7") (pinfunction "7_7") (pintype "bidirectional"))
      (node (ref "U7") (pin "13") (pinfunction "I_IN_13") (pintype "bidirectional"))
    )
    (net (code "13") (name "LNA_EN") (class "Default")
      (node (ref "C5") (pin "1") (pinfunction "1_1") (pintype "passive"))
      (node (ref "R2") (pin "1") (pinfunction "1_1") (pintype "passive"))
      (node (ref "U10") (pin "3") (pinfunction "CPS_3") (pintype "bidirectional"))
    )
    (net (code "14") (name "MISO_A") (class "Default")
      (node (ref "U1") (pin "62") (pinfunction "RADIO_A_MISO_62") (pintype "bidirectional"))
      (node (ref "U7") (pin "18") (pinfunction "MISO_18") (pintype "bidirectional"))
    )
    (net (code "15") (name "MISO_B") (class "Default")
      (node (ref "U1") (pin "21") (pinfunction "RADIO_B_MISO_21") (pintype "bidirectional"))
      (node (ref "U6") (pin "18") (pinfunction "MISO_18") (pintype "bidirectional"))
    )
    (net (code "16") (name "MOSI_A") (class "Default")
      (node (ref "U1") (pin "63") (pinfunction "RADIO_A_MOSI_63") (pintype "bidirectional"))
      (node (ref "U7") (pin "19") (pinfunction "MOSI_19") (pintype "bidirectional"))
    )
    (net (code "17") (name "MOSI_B") (class "Default")
      (node (ref "U1") (pin "20") (pinfunction "RADIO_B_MOSI_20") (pintype "bidirectional"))
      (node (ref "U6") (pin "19") (pinfunction "MOSI_19") (pintype "bidirectional"))
    )
    (net (code "18") (name "NSS_A") (class "Default")
      (node (ref "U1") (pin "64") (pinfunction "RADIO_A_CS_64") (pintype "bidirectional"))
      (node (ref "U7") (pin "20") (pinfunction "NSS_20") (pintype "bidirectional"))
    )
    (net (code "19") (name "NSS_B") (class "Default")
      (node (ref "U1") (pin "19") (pinfunction "RADIO_B_CS_19") (pintype "bidirectional"))
      (node (ref "U6") (pin "20") (pinfunction "NSS_20") (pintype "bidirectional"))
    )
    (net (code "20") (name "Net-(C9-Pad1)") (class "Default")
      (node (ref "C9") (pin "1") (pinfunction "1_1") (pintype "passive"))
      (node (ref "U1") (pin "23") (pinfunction "VCC18_23") (pintype "bidirectional"))
    )
    (net (code "21") (name "Net-(C11-Pad1)") (class "Default")
      (node (ref "C11") (pin "1") (pinfunction "1_1") (pintype "passive"))
      (node (ref "C12") (pin "1") (pinfunction "1_1") (pintype "passive"))
      (node (ref "U1") (pin "52") (pinfunction "VCC33_52") (pintype "bidirectional"))
    )
    (net (code "22") (name "Net-(C47-Pad1)") (class "Default")
      (node (ref "C47") (pin "1") (pinfunction "1_1") (pintype "passive"))
      (node (ref "L4") (pin "1") (pinfunction "1_1") (pintype "passive"))
    )
    (net (code "23") (name "Net-(C51-Pad2)") (class "Default")
      (node (ref "C51") (pin "2") (pinfunction "2_2") (pintype "passive"))
      (node (ref "R22") (pin "1") (pinfunction "1_1") (pintype "passive"))
      (node (ref "R23") (pin "1") (pinfunction "1_1") (pintype "passive"))
    )
    (net (code "24") (name "Net-(C58-Pad1)") (class "Default")
      (node (ref "C58") (pin "1") (pinfunction "1_1") (pintype "passive"))
      (node (ref "C61") (pin "1") (pinfunction "1_1") (pintype "passive"))
      (node (ref "L11") (pin "2") (pinfunction "2_2") (pintype "passive"))
      (node (ref "L8") (pin "1") (pinfunction "1_1") (pintype "passive"))
    )
    (net (code "25") (name "Net-(C59-Pad2)") (class "Default")
      (node (ref "C59") (pin "2") (pinfunction "2_2") (pintype "passive"))
      (node (ref "C60") (pin "1") (pinfunction "1_1") (pintype "passive"))
      (node (ref "L10") (pin "2") (pinfunction "2_2") (pintype "passive"))
      (node (ref "L9") (pin "1") (pinfunction "1_1") (pintype "passive"))
    )
    (net (code "26") (name "Net-(C62-Pad1)") (class "Default")
      (node (ref "C62") (pin "1") (pinfunction "1_1") (pintype "passive"))
      (node (ref "C64") (pin "1") (pinfunction "1_1") (pintype "passive"))
      (node (ref "D9") (pin "1") (pinfunction "1_1") (pintype "bidirectional"))
      (node (ref "L10") (pin "1") (pinfunction "1_1") (pintype "passive"))
    )
    (net (code "27") (name "Net-(C64-Pad2)") (class "Default")
      (node (ref "C64") (pin "2") (pinfunction "2_2") (pintype "passive"))
      (node (ref "X4") (pin "1") (pinfunction "1_1") (pintype "bidirectional"))
    )
    (net (code "28") (name "Net-(D1-PadA)") (class "Default")
      (node (ref "D1") (pin "A") (pinfunction "A_A") (pintype "passive"))
      (node (ref "R8") (pin "1") (pinfunction "1_1") (pintype "passive"))
    )
    (net (code "29") (name "Net-(D2-PadA)") (class "Default")
      (node (ref "D2") (pin "A") (pinfunction "A_A") (pintype "passive"))
      (node (ref "R7") (pin "2") (pinfunction "2_2") (pintype "passive"))
    )
    (net (code "30") (name "Net-(D3-PadA)") (class "Default")
      (node (ref "D3") (pin "A") (pinfunction "A_A") (pintype "passive"))
      (node (ref "R9") (pin "2") (pinfunction "2_2") (pintype "passive"))
    )
    (net (code "31") (name "Net-(D4-PadA)") (class "Default")
      (node (ref "D4") (pin "A") (pinfunction "A_A") (pintype "passive"))
      (node (ref "R11") (pin "2") (pinfunction "2_2") (pintype "passive"))
    )
    (net (code "32") (name "Net-(D5-PadA)") (class "Default")
      (node (ref "D5") (pin "A") (pinfunction "A_A") (pintype "passive"))
      (node (ref "R14") (pin "2") (pinfunction "2_2") (pintype "passive"))
    )
    (net (code "33") (name "Net-(D6-PadA)") (class "Default")
      (node (ref "D6") (pin "A") (pinfunction "A_A") (pintype "passive"))
      (node (ref "R15") (pin "2") (pinfunction "2_2") (pintype "passive"))
    )
    (net (code "34") (name "Net-(U1-A_IQ_RX)") (class "Default")
      (node (ref "R12") (pin "4") (pinfunction "4_4") (pintype "bidirectional"))
      (node (ref "U1") (pin "44") (pinfunction "A_IQ_RX_44") (pintype "bidirectional"))
    )
    (net (code "35") (name "Net-(U1-A_IQ_TX)") (class "Default")
      (node (ref "R12") (pin "2") (pinfunction "2_2") (pintype "bidirectional"))
      (node (ref "U1") (pin "46") (pinfunction "A_IQ_TX_46") (pintype "bidirectional"))
    )
    (net (code "36") (name "Net-(U1-A_QI_RX)") (class "Default")
      (node (ref "R12") (pin "3") (pinfunction "3_3") (pintype "bidirectional"))
      (node (ref "U1") (pin "45") (pinfunction "A_QI_RX_45") (pintype "bidirectional"))
    )
    (net (code "37") (name "Net-(U1-A_QI_TX)") (class "Default")
      (node (ref "R12") (pin "1") (pinfunction "1_1") (pintype "bidirectional"))
      (node (ref "U1") (pin "47") (pinfunction "A_QI_TX_47") (pintype "bidirectional"))
    )
    (net (code "38") (name "Net-(U1-B_IQ_RX)") (class "Default")
      (node (ref "R13") (pin "4") (pinfunction "4_4") (pintype "bidirectional"))
      (node (ref "U1") (pin "35") (pinfunction "B_IQ_RX_35") (pintype "bidirectional"))
    )
    (net (code "39") (name "Net-(U1-B_QI_RX)") (class "Default")
      (node (ref "R13") (pin "3") (pinfunction "3_3") (pintype "bidirectional"))
      (node (ref "U1") (pin "36") (pinfunction "B_QI_RX_36") (pintype "bidirectional"))
    )
    (net (code "40") (name "Net-(U1-CLK32M)") (class "Default")
      (node (ref "R10") (pin "1") (pinfunction "1_1") (pintype "passive"))
      (node (ref "U1") (pin "43") (pinfunction "CLK32M_43") (pintype "bidirectional"))
    )
    (net (code "41") (name "Net-(U1-GPIO[0])") (class "Default")
      (node (ref "R15") (pin "1") (pinfunction "1_1") (pintype "passive"))
      (node (ref "U1") (pin "58") (pinfunction "GPIO[0]_58") (pintype "bidirectional"))
    )
    (net (code "42") (name "Net-(U1-GPIO[2])") (class "Default")
      (node (ref "R11") (pin "1") (pinfunction "1_1") (pintype "passive"))
      (node (ref "U1") (pin "56") (pinfunction "GPIO[2]_56") (pintype "bidirectional"))
    )
    (net (code "43") (name "Net-(U1-GPIO[3])") (class "Default")
      (node (ref "R9") (pin "1") (pinfunction "1_1") (pintype "passive"))
      (node (ref "U1") (pin "55") (pinfunction "GPIO[3]_55") (pintype "bidirectional"))
    )
    (net (code "44") (name "Net-(U1-HOST_CSN)") (class "Default")
      (node (ref "R4") (pin "5") (pinfunction "5_5") (pintype "bidirectional"))
      (node (ref "U1") (pin "5") (pinfunction "HOST_CSN_5") (pintype "bidirectional"))
    )
    (net (code "45") (name "Net-(U1-HOST_MISO)") (class "Default")
      (node (ref "R4") (pin "7") (pinfunction "7_7") (pintype "bidirectional"))
      (node (ref "U1") (pin "3") (pinfunction "HOST_MISO_3") (pintype "bidirectional"))
    )
    (net (code "46") (name "Net-(U1-HOST_MOSI)") (class "Default")
      (node (ref "R4") (pin "6") (pinfunction "6_6") (pintype "bidirectional"))
      (node (ref "U1") (pin "4") (pinfunction "HOST_MOSI_4") (pintype "bidirectional"))
    )
    (net (code "47") (name "Net-(U1-HOST_SCK)") (class "Default")
      (node (ref "R4") (pin "8") (pinfunction "8_8") (pintype "bidirectional"))
      (node (ref "U1") (pin "2") (pinfunction "HOST_SCK_2") (pintype "bidirectional"))
    )
    (net (code "48") (name "Net-(U1-LNA_A_CTRL)") (class "Default")
      (node (ref "R2") (pin "2") (pinfunction "2_2") (pintype "passive"))
      (node (ref "U1") (pin "14") (pinfunction "LNA_A_CTRL_14") (pintype "bidirectional"))
    )
    (net (code "49") (name "Net-(U1-PA_A_CTRL)") (class "Default")
      (node (ref "R3") (pin "2") (pinfunction "2_2") (pintype "passive"))
      (node (ref "U1") (pin "15") (pinfunction "PA_A_CTRL_15") (pintype "bidirectional"))
    )
    (net (code "50") (name "Net-(U1-SP_CLK_OUT)") (class "Default")
      (node (ref "R6") (pin "1") (pinfunction "1_1") (pintype "passive"))
      (node (ref "U1") (pin "39") (pinfunction "SP_CLK_OUT_39") (pintype "bidirectional"))
    )
    (net (code "51") (name "Net-(U2-3DFIX)") (class "Default")
      (node (ref "R8") (pin "2") (pinfunction "2_2") (pintype "passive"))
      (node (ref "U2") (pin "5") (pinfunction "3DFIX_5") (pintype "bidirectional"))
    )
    (net (code "52") (name "Net-(U2-EX_ANT)") (class "Default")
      (node (ref "U2") (pin "11") (pinfunction "EX_ANT_11") (pintype "bidirectional"))
      (node (ref "X2") (pin "1") (pinfunction "1_1") (pintype "bidirectional"))
    )
    (net (code "53") (name "Net-(U3-EN)") (class "Default")
      (node (ref "C17") (pin "1") (pinfunction "1_1") (pintype "passive"))
      (node (ref "FB3") (pin "2") (pinfunction "2_2") (pintype "passive"))
      (node (ref "U3") (pin "2") (pinfunction "EN_2") (pintype "bidirectional"))
      (node (ref "U3") (pin "3") (pinfunction "VIN_3") (pintype "bidirectional"))
    )
    (net (code "54") (name "Net-(U3-FB)") (class "Default")
      (node (ref "R18") (pin "1") (pinfunction "1_1") (pintype "passive"))
      (node (ref "R19") (pin "2") (pinfunction "2_2") (pintype "passive"))
      (node (ref "U3") (pin "7") (pinfunction "FB_7") (pintype "bidirectional"))
    )
    (net (code "55") (name "Net-(U4-LXA)") (class "Default")
      (node (ref "L1") (pin "1") (pinfunction "1_1") (pintype "passive"))
      (node (ref "U4") (pin "2") (pinfunction "LXA_2") (pintype "bidirectional"))
    )
    (net (code "56") (name "Net-(U4-LXB)") (class "Default")
      (node (ref "L2") (pin "2") (pinfunction "2_2") (pintype "passive"))
      (node (ref "U4") (pin "11") (pinfunction "LXB_11") (pintype "bidirectional"))
    )
    (net (code "57") (name "Net-(U5-BYP)") (class "Default")
      (node (ref "C24") (pin "1") (pinfunction "1_1") (pintype "passive"))
      (node (ref "U5") (pin "7") (pinfunction "BYP_7") (pintype "bidirectional"))
    )
    (net (code "58") (name "Net-(U6-RESET)") (class "Default")
      (node (ref "D7") (pin "C") (pinfunction "C_C") (pintype "passive"))
      (node (ref "U6") (pin "9") (pinfunction "RESET_9") (pintype "bidirectional"))
    )
    (net (code "59") (name "Net-(U6-RF_IN)") (class "Default")
      (node (ref "L3") (pin "1") (pinfunction "1_1") (pintype "passive"))
      (node (ref "L4") (pin "2") (pinfunction "2_2") (pintype "passive"))
      (node (ref "U6") (pin "27") (pinfunction "RF_IN_27") (pintype "bidirectional"))
      (node (ref "U7") (pin "27") (pinfunction "RF_IN_27") (pintype "bidirectional"))
    )
    (net (code "60") (name "Net-(U6-VR_ANA1)") (class "Default")
      (node (ref "C35") (pin "2") (pinfunction "2_2") (pintype "passive"))
      (node (ref "U6") (pin "3") (pinfunction "VR_ANA1_3") (pintype "bidirectional"))
    )
    (net (code "61") (name "Net-(U6-VR_ANA2)") (class "Default")
      (node (ref "C39") (pin "1") (pinfunction "1_1") (pintype "passive"))
      (node (ref "U6") (pin "25") (pinfunction "VR_ANA2_25") (pintype "bidirectional"))
    )
    (net (code "62") (name "Net-(U6-VR_DIG)") (class "Default")
      (node (ref "C33") (pin "2") (pinfunction "2_2") (pintype "passive"))
      (node (ref "U6") (pin "5") (pinfunction "VR_DIG_5") (pintype "bidirectional"))
    )
    (net (code "63") (name "Net-(U6-VR_PA)") (class "Default")
      (node (ref "C37") (pin "2") (pinfunction "2_2") (pintype "passive"))
      (node (ref "U6") (pin "1") (pinfunction "VR_PA_1") (pintype "bidirectional"))
    )
    (net (code "64") (name "Net-(U6-XTB)") (class "Default")
      (node (ref "C31") (pin "1") (pinfunction "1_1") (pintype "passive"))
      (node (ref "U6") (pin "8") (pinfunction "XTB_8") (pintype "bidirectional"))
    )
    (net (code "65") (name "Net-(U7-RESET)") (class "Default")
      (node (ref "D8") (pin "C") (pinfunction "C_C") (pintype "passive"))
      (node (ref "U7") (pin "9") (pinfunction "RESET_9") (pintype "bidirectional"))
    )
    (net (code "66") (name "Net-(U7-RF_ON)") (class "Default")
      (node (ref "C43") (pin "1") (pinfunction "1_1") (pintype "passive"))
      (node (ref "U7") (pin "29") (pinfunction "RF_ON_29") (pintype "bidirectional"))
    )
    (net (code "67") (name "Net-(U7-RF_OP)") (class "Default")
      (node (ref "C46") (pin "1") (pinfunction "1_1") (pintype "passive"))
      (node (ref "U7") (pin "30") (pinfunction "RF_OP_30") (pintype "bidirectional"))
    )
    (net (code "68") (name "Net-(U7-VR_ANA1)") (class "Default")
      (node (ref "C36") (pin "2") (pinfunction "2_2") (pintype "passive"))
      (node (ref "U7") (pin "3") (pinfunction "VR_ANA1_3") (pintype "bidirectional"))
    )
    (net (code "69") (name "Net-(U7-VR_ANA2)") (class "Default")
      (node (ref "C40") (pin "1") (pinfunction "1_1") (pintype "passive"))
      (node (ref "U7") (pin "25") (pinfunction "VR_ANA2_25") (pintype "bidirectional"))
    )
    (net (code "70") (name "Net-(U7-VR_DIG)") (class "Default")
      (node (ref "C34") (pin "2") (pinfunction "2_2") (pintype "passive"))
      (node (ref "U7") (pin "5") (pinfunction "VR_DIG_5") (pintype "bidirectional"))
    )
    (net (code "71") (name "Net-(U7-VR_PA)") (class "Default")
      (node (ref "C38") (pin "2") (pinfunction "2_2") (pintype "passive"))
      (node (ref "U7") (pin "1") (pinfunction "VR_PA_1") (pintype "bidirectional"))
    )
    (net (code "72") (name "Net-(U7-XTB)") (class "Default")
      (node (ref "C32") (pin "1") (pinfunction "1_1") (pintype "passive"))
      (node (ref "U7") (pin "8") (pinfunction "XTB_8") (pintype "bidirectional"))
    )
    (net (code "73") (name "Net-(U8-IN)") (class "Default")
      (node (ref "C46") (pin "2") (pinfunction "2_2") (pintype "passive"))
      (node (ref "U8") (pin "2") (pinfunction "IN_2") (pintype "bidirectional"))
    )
    (net (code "74") (name "Net-(U8-OUT)") (class "Default")
      (node (ref "R21") (pin "1") (pinfunction "1_1") (pintype "passive"))
      (node (ref "R22") (pin "2") (pinfunction "2_2") (pintype "passive"))
      (node (ref "U8") (pin "5") (pinfunction "OUT_5") (pintype "bidirectional"))
    )
    (net (code "75") (name "Net-(U9-IN)") (class "Default")
      (node (ref "C50") (pin "1") (pinfunction "1_1") (pintype "passive"))
      (node (ref "U9") (pin "2") (pinfunction "IN_2") (pintype "bidirectional"))
    )
    (net (code "76") (name "Net-(U9-OUT)") (class "Default")
      (node (ref "C47") (pin "2") (pinfunction "2_2") (pintype "passive"))
      (node (ref "C48") (pin "1") (pinfunction "1_1") (pintype "passive"))
      (node (ref "U9") (pin "5") (pinfunction "OUT_5") (pintype "bidirectional"))
    )
    (net (code "77") (name "Net-(U10-ANT1)") (class "Default")
      (node (ref "C57") (pin "1") (pinfunction "1_1") (pintype "passive"))
      (node (ref "C59") (pin "1") (pinfunction "1_1") (pintype "passive"))
      (node (ref "L9") (pin "2") (pinfunction "2_2") (pintype "passive"))
      (node (ref "U10") (pin "14") (pinfunction "ANT1_14") (pintype "bidirectional"))
    )
    (net (code "78") (name "Net-(U10-ANT2)") (class "Default")
      (node (ref "R25") (pin "2") (pinfunction "2_2") (pintype "passive"))
      (node (ref "U10") (pin "12") (pinfunction "ANT2_12") (pintype "bidirectional"))
    )
    (net (code "79") (name "Net-(U10-LNA_IN)") (class "Default")
      (node (ref "U10") (pin "9") (pinfunction "LNA_IN_9") (pintype "bidirectional"))
      (node (ref "U11") (pin "5") (pinfunction "OUT_5") (pintype "bidirectional"))
    )
    (net (code "80") (name "Net-(U10-PA_IN)") (class "Default")
      (node (ref "C51") (pin "1") (pinfunction "1_1") (pintype "passive"))
      (node (ref "U10") (pin "2") (pinfunction "PA_IN_2") (pintype "bidirectional"))
    )
    (net (code "81") (name "Net-(U10-PA_OUT)") (class "Default")
      (node (ref "L8") (pin "2") (pinfunction "2_2") (pintype "passive"))
      (node (ref "U10") (pin "20") (pinfunction "PA_OUT_20") (pintype "bidirectional"))
    )
    (net (code "82") (name "Net-(U10-RX_FLT)") (class "Default")
      (node (ref "U10") (pin "11") (pinfunction "RX_FLT_11") (pintype "bidirectional"))
      (node (ref "U11") (pin "2") (pinfunction "IN_2") (pintype "bidirectional"))
    )
    (net (code "83") (name "Net-(U10-TR)") (class "Default")
      (node (ref "C50") (pin "2") (pinfunction "2_2") (pintype "passive"))
      (node (ref "U10") (pin "6") (pinfunction "TR_6") (pintype "bidirectional"))
    )
    (net (code "84") (name "Net-(U10-TX_FLT)") (class "Default")
      (node (ref "R24") (pin "2") (pinfunction "2_2") (pintype "passive"))
      (node (ref "U10") (pin "5") (pinfunction "TX_FLT_5") (pintype "bidirectional"))
    )
    (net (code "85") (name "Net-(U10-TX_IN)") (class "Default")
      (node (ref "C63") (pin "1") (pinfunction "1_1") (pintype "passive"))
      (node (ref "L11") (pin "1") (pinfunction "1_1") (pintype "passive"))
      (node (ref "U10") (pin "16") (pinfunction "TX_IN_16") (pintype "bidirectional"))
    )
    (net (code "86") (name "Net-(U10-VCC0)") (class "Default")
      (node (ref "C54") (pin "1") (pinfunction "1_1") (pintype "passive"))
      (node (ref "L6") (pin "1") (pinfunction "1_1") (pintype "passive"))
      (node (ref "U10") (pin "23") (pinfunction "VCC0_23") (pintype "bidirectional"))
    )
    (net (code "87") (name "Net-(U10-VCC1)") (class "Default")
      (node (ref "C53") (pin "1") (pinfunction "1_1") (pintype "passive"))
      (node (ref "L5") (pin "1") (pinfunction "1_1") (pintype "passive"))
      (node (ref "U10") (pin "24") (pinfunction "VCC1_24") (pintype "bidirectional"))
    )
    (net (code "88") (name "Net-(U10-VCC2)") (class "Default")
      (node (ref "L7") (pin "2") (pinfunction "2_2") (pintype "passive"))
      (node (ref "U10") (pin "21") (pinfunction "VCC2_21") (pintype "bidirectional"))
    )
    (net (code "89") (name "Net-(X1-OUT)") (class "Default")
      (node (ref "R5") (pin "1") (pinfunction "1_1") (pintype "passive"))
      (node (ref "X1") (pin "3") (pinfunction "OUT_3") (pintype "bidirectional"))
    )
    (net (code "90") (name "Net-(X1-SBY)") (class "Default")
      (node (ref "C2") (pin "1") (pinfunction "1_1") (pintype "passive"))
      (node (ref "FB1") (pin "2") (pinfunction "2_2") (pintype "passive"))
      (node (ref "X1") (pin "1") (pinfunction "SBY_1") (pintype "bidirectional"))
      (node (ref "X1") (pin "4") (pinfunction "VCC_4") (pintype "bidirectional"))
    )
    (net (code "91") (name "Net-(X3-VCC)") (class "Default")
      (node (ref "C28") (pin "1") (pinfunction "1_1") (pintype "passive"))
      (node (ref "FB4") (pin "2") (pinfunction "2_2") (pintype "passive"))
      (node (ref "X3") (pin "4") (pinfunction "VCC_4") (pintype "bidirectional"))
    )
    (net (code "92") (name "PA_EN") (class "Default")
      (node (ref "C6") (pin "1") (pinfunction "1_1") (pintype "passive"))
      (node (ref "R3") (pin "1") (pinfunction "1_1") (pintype "passive"))
      (node (ref "U10") (pin "4") (pinfunction "CTX_4") (pintype "bidirectional"))
    )
    (net (code "93") (name "PPS") (class "Default")
      (node (ref "J1") (pin "18") (pinfunction "GEN5/GPIO24_18") (pintype "bidirectional"))
      (node (ref "U1") (pin "9") (pinfunction "GPS_IN_9") (pintype "bidirectional"))
      (node (ref "U2") (pin "13") (pinfunction "PPS_13") (pintype "bidirectional"))
    )
    (net (code "94") (name "QRXD_A") (class "Default")
      (node (ref "R12") (pin "6") (pinfunction "6_6") (pintype "bidirectional"))
      (node (ref "U7") (pin "14") (pinfunction "Q_OUT_14") (pintype "bidirectional"))
    )
    (net (code "95") (name "QRXD_B") (class "Default")
      (node (ref "R13") (pin "6") (pinfunction "6_6") (pintype "bidirectional"))
      (node (ref "U6") (pin "14") (pinfunction "Q_OUT_14") (pintype "bidirectional"))
    )
    (net (code "96") (name "QTXD_A") (class "Default")
      (node (ref "R12") (pin "8") (pinfunction "8_8") (pintype "bidirectional"))
      (node (ref "U7") (pin "12") (pinfunction "Q_IN_12") (pintype "bidirectional"))
    )
    (net (code "97") (name "RADIO_EN_A") (class "Default")
      (node (ref "R16") (pin "2") (pinfunction "2_2") (pintype "passive"))
      (node (ref "U5") (pin "6") (pinfunction "ENA_6") (pintype "bidirectional"))
    )
    (net (code "98") (name "RADIO_EN_B") (class "Default")
      (node (ref "R17") (pin "2") (pinfunction "2_2") (pintype "passive"))
      (node (ref "U5") (pin "4") (pinfunction "ENB_4") (pintype "bidirectional"))
    )
    (net (code "99") (name "RADIO_RST") (class "Default")
      (node (ref "D7") (pin "A") (pinfunction "A_A") (pintype "passive"))
      (node (ref "D8") (pin "A") (pinfunction "A_A") (pintype "passive"))
      (node (ref "U1") (pin "25") (pinfunction "RADIO_RST_25") (pintype "bidirectional"))
    )
    (net (code "100") (name "RESET") (class "Default")
      (node (ref "J1") (pin "22") (pinfunction "GEN/6GPIO25_22") (pintype "bidirectional"))
      (node (ref "R1") (pin "2") (pinfunction "2_2") (pintype "passive"))
      (node (ref "U1") (pin "1") (pinfunction "RESET_1") (pintype "bidirectional"))
    )
    (net (code "101") (name "RX_ON") (class "Default")
      (node (ref "R14") (pin "1") (pinfunction "1_1") (pintype "passive"))
      (node (ref "U1") (pin "57") (pinfunction "GPIO[1]_57") (pintype "bidirectional"))
    )
    (net (code "102") (name "SCK_A") (class "Default")
      (node (ref "U1") (pin "61") (pinfunction "RADIO_A_SCK_61") (pintype "bidirectional"))
      (node (ref "U7") (pin "17") (pinfunction "SCK_17") (pintype "bidirectional"))
    )
    (net (code "103") (name "SCK_B") (class "Default")
      (node (ref "U1") (pin "22") (pinfunction "RADIO_B_SCK_22") (pintype "bidirectional"))
      (node (ref "U6") (pin "17") (pinfunction "SCK_17") (pintype "bidirectional"))
    )
    (net (code "104") (name "SPI_MISO") (class "Default")
      (node (ref "J1") (pin "21") (pinfunction "GPIO9/MISO_21") (pintype "bidirectional"))
      (node (ref "R4") (pin "2") (pinfunction "2_2") (pintype "bidirectional"))
    )
    (net (code "105") (name "SPI_MOSI") (class "Default")
      (node (ref "J1") (pin "19") (pinfunction "GPIO10/MOSI_19") (pintype "bidirectional"))
      (node (ref "R4") (pin "3") (pinfunction "3_3") (pintype "bidirectional"))
    )
    (net (code "106") (name "SPI_NSS") (class "Default")
      (node (ref "J1") (pin "24") (pinfunction "~{CE0}/GPIO8_24") (pintype "bidirectional"))
      (node (ref "R4") (pin "4") (pinfunction "4_4") (pintype "bidirectional"))
    )
    (net (code "107") (name "SPI_SCK") (class "Default")
      (node (ref "J1") (pin "23") (pinfunction "GPIO11/SCLK_23") (pintype "bidirectional"))
      (node (ref "R4") (pin "1") (pinfunction "1_1") (pintype "bidirectional"))
    )
    (net (code "108") (name "TX_ON") (class "Default")
      (node (ref "R7") (pin "1") (pinfunction "1_1") (pintype "passive"))
      (node (ref "U1") (pin "54") (pinfunction "GPIO[4]_54") (pintype "bidirectional"))
    )
    (net (code "109") (name "V+") (class "Default")
      (node (ref "C13") (pin "1") (pinfunction "1_1") (pintype "passive"))
      (node (ref "J1") (pin "1") (pinfunction "3V3_1") (pintype "power_in"))
      (node (ref "U2") (pin "1") (pinfunction "VCC_1") (pintype "bidirectional"))
      (node (ref "U2") (pin "2") (pinfunction "~{RESET}_2") (pintype "bidirectional"))
    )
    (net (code "110") (name "VCC") (class "Default")
      (node (ref "C14") (pin "1") (pinfunction "1_1") (pintype "passive"))
      (node (ref "C26") (pin "1") (pinfunction "1_1") (pintype "passive"))
      (node (ref "FB2") (pin "1") (pinfunction "1_1") (pintype "passive"))
      (node (ref "L2") (pin "1") (pinfunction "1_1") (pintype "passive"))
      (node (ref "U4") (pin "9") (pinfunction "VOUTB_9") (pintype "bidirectional"))
    )
    (net (code "111") (name "VCCA_A") (class "Default")
      (node (ref "C25") (pin "1") (pinfunction "1_1") (pintype "passive"))
      (node (ref "C30") (pin "1") (pinfunction "1_1") (pintype "passive"))
      (node (ref "C42") (pin "1") (pinfunction "1_1") (pintype "passive"))
      (node (ref "C45") (pin "1") (pinfunction "1_1") (pintype "passive"))
      (node (ref "C52") (pin "1") (pinfunction "1_1") (pintype "passive"))
      (node (ref "FB4") (pin "1") (pinfunction "1_1") (pintype "passive"))
      (node (ref "L6") (pin "2") (pinfunction "2_2") (pintype "passive"))
      (node (ref "U5") (pin "3") (pinfunction "OUTA_3") (pintype "bidirectional"))
      (node (ref "U7") (pin "16") (pinfunction "VBAT2_16") (pintype "bidirectional"))
      (node (ref "U7") (pin "2") (pinfunction "VBAT1_2") (pintype "bidirectional"))
      (node (ref "U7") (pin "32") (pinfunction "VBAT3_32") (pintype "bidirectional"))
    )
    (net (code "112") (name "VCCA_B") (class "Default")
      (node (ref "C27") (pin "1") (pinfunction "1_1") (pintype "passive"))
      (node (ref "C29") (pin "1") (pinfunction "1_1") (pintype "passive"))
      (node (ref "C41") (pin "1") (pinfunction "1_1") (pintype "passive"))
      (node (ref "C44") (pin "1") (pinfunction "1_1") (pintype "passive"))
      (node (ref "U5") (pin "1") (pinfunction "OUTB_1") (pintype "bidirectional"))
      (node (ref "U6") (pin "16") (pinfunction "VBAT2_16") (pintype "bidirectional"))
      (node (ref "U6") (pin "2") (pinfunction "VBAT1_2") (pintype "bidirectional"))
      (node (ref "U6") (pin "32") (pinfunction "VBAT3_32") (pintype "bidirectional"))
    )
    (net (code "113") (name "VCCDIG18") (class "Default")
      (node (ref "C15") (pin "1") (pinfunction "1_1") (pintype "passive"))
      (node (ref "C16") (pin "1") (pinfunction "1_1") (pintype "passive"))
      (node (ref "C3") (pin "1") (pinfunction "1_1") (pintype "passive"))
      (node (ref "C4") (pin "1") (pinfunction "1_1") (pintype "passive"))
      (node (ref "C7") (pin "1") (pinfunction "1_1") (pintype "passive"))
      (node (ref "C8") (pin "1") (pinfunction "1_1") (pintype "passive"))
      (node (ref "FB2") (pin "2") (pinfunction "2_2") (pintype "passive"))
      (node (ref "U1") (pin "12") (pinfunction "VCC18_12") (pintype "bidirectional"))
      (node (ref "U1") (pin "42") (pinfunction "VCC18_42") (pintype "bidirectional"))
      (node (ref "U1") (pin "60") (pinfunction "VCC18_60") (pintype "bidirectional"))
      (node (ref "U1") (pin "8") (pinfunction "VCC18_8") (pintype "bidirectional"))
    )
    (net (code "114") (name "VCCDIG33") (class "Default")
      (node (ref "C1") (pin "1") (pinfunction "1_1") (pintype "passive"))
      (node (ref "C10") (pin "1") (pinfunction "1_1") (pintype "passive"))
      (node (ref "C18") (pin "1") (pinfunction "1_1") (pintype "passive"))
      (node (ref "FB1") (pin "1") (pinfunction "1_1") (pintype "passive"))
      (node (ref "FB3") (pin "1") (pinfunction "1_1") (pintype "passive"))
      (node (ref "L1") (pin "2") (pinfunction "2_2") (pintype "passive"))
      (node (ref "U1") (pin "29") (pinfunction "VCC33_29") (pintype "bidirectional"))
      (node (ref "U4") (pin "18") (pinfunction "VOUTA_18") (pintype "bidirectional"))
    )
    (net (code "115") (name "VCCINT") (class "Default")
      (node (ref "C21") (pin "1") (pinfunction "1_1") (pintype "passive"))
      (node (ref "C22") (pin "1") (pinfunction "1_1") (pintype "passive"))
      (node (ref "FB5") (pin "1") (pinfunction "1_1") (pintype "passive"))
      (node (ref "R18") (pin "2") (pinfunction "2_2") (pintype "passive"))
      (node (ref "R20") (pin "1") (pinfunction "1_1") (pintype "passive"))
      (node (ref "U3") (pin "6") (pinfunction "VOUT_6") (pintype "bidirectional"))
    )
    (net (code "116") (name "VCC_FEM") (class "Default")
      (node (ref "C49") (pin "1") (pinfunction "1_1") (pintype "passive"))
      (node (ref "C55") (pin "1") (pinfunction "1_1") (pintype "passive"))
      (node (ref "C56") (pin "1") (pinfunction "1_1") (pintype "passive"))
      (node (ref "FB5") (pin "2") (pinfunction "2_2") (pintype "passive"))
      (node (ref "L5") (pin "2") (pinfunction "2_2") (pintype "passive"))
      (node (ref "L7") (pin "1") (pinfunction "1_1") (pintype "passive"))
    )
    (net (code "117") (name "XTL_OUT") (class "Default")
      (node (ref "C31") (pin "2") (pinfunction "2_2") (pintype "passive"))
      (node (ref "C32") (pin "2") (pinfunction "2_2") (pintype "passive"))
      (node (ref "X3") (pin "3") (pinfunction "OUT_3") (pintype "bidirectional"))
    )
    (net (code "118") (name "unconnected-(J1-GEN4{slash}GPIO23-Pad16)") (class "Default")
      (node (ref "J1") (pin "16") (pinfunction "GEN4/GPIO23_16") (pintype "bidirectional"))
    )
    (net (code "119") (name "unconnected-(J1-GPIO2{slash}SDA1-Pad3)") (class "Default")
      (node (ref "J1") (pin "3") (pinfunction "GPIO2/SDA1_3") (pintype "bidirectional"))
    )
    (net (code "120") (name "unconnected-(J1-GPIO3{slash}SCL1-Pad5)") (class "Default")
      (node (ref "J1") (pin "5") (pinfunction "GPIO3/SCL1_5") (pintype "bidirectional"))
    )
    (net (code "121") (name "unconnected-(J1-GPIO4{slash}GCKL-Pad7)") (class "Default")
      (node (ref "J1") (pin "7") (pinfunction "GPIO4/GCKL_7") (pintype "bidirectional"))
    )
    (net (code "122") (name "unconnected-(J1-GPIO5-Pad29)") (class "Default")
      (node (ref "J1") (pin "29") (pinfunction "GPIO5_29") (pintype "bidirectional"))
    )
    (net (code "123") (name "unconnected-(J1-GPIO6-Pad31)") (class "Default")
      (node (ref "J1") (pin "31") (pinfunction "GPIO6_31") (pintype "bidirectional"))
    )
    (net (code "124") (name "unconnected-(J1-GPIO12-Pad32)") (class "Default")
      (node (ref "J1") (pin "32") (pinfunction "GPIO12_32") (pintype "bidirectional"))
    )
    (net (code "125") (name "unconnected-(J1-GPIO13-Pad33)") (class "Default")
      (node (ref "J1") (pin "33") (pinfunction "GPIO13_33") (pintype "bidirectional"))
    )
    (net (code "126") (name "unconnected-(J1-GPIO16-Pad36)") (class "Default")
      (node (ref "J1") (pin "36") (pinfunction "GPIO16_36") (pintype "bidirectional"))
    )
    (net (code "127") (name "unconnected-(J1-GPIO17{slash}GEN0-Pad11)") (class "Default")
      (node (ref "J1") (pin "11") (pinfunction "GPIO17/GEN0_11") (pintype "bidirectional"))
    )
    (net (code "128") (name "unconnected-(J1-GPIO18-Pad12)") (class "Default")
      (node (ref "J1") (pin "12") (pinfunction "GPIO18_12") (pintype "bidirectional"))
    )
    (net (code "129") (name "unconnected-(J1-GPIO19-Pad35)") (class "Default")
      (node (ref "J1") (pin "35") (pinfunction "GPIO19_35") (pintype "bidirectional"))
    )
    (net (code "130") (name "unconnected-(J1-GPIO20-Pad38)") (class "Default")
      (node (ref "J1") (pin "38") (pinfunction "GPIO20_38") (pintype "bidirectional"))
    )
    (net (code "131") (name "unconnected-(J1-GPIO21-Pad40)") (class "Default")
      (node (ref "J1") (pin "40") (pinfunction "GPIO21_40") (pintype "bidirectional"))
    )
    (net (code "132") (name "unconnected-(J1-GPIO22{slash}GEN3-Pad15)") (class "Default")
      (node (ref "J1") (pin "15") (pinfunction "GPIO22/GEN3_15") (pintype "bidirectional"))
    )
    (net (code "133") (name "unconnected-(J1-GPIO26-Pad37)") (class "Default")
      (node (ref "J1") (pin "37") (pinfunction "GPIO26_37") (pintype "bidirectional"))
    )
    (net (code "134") (name "unconnected-(J1-GPIO27{slash}GEN2-Pad13)") (class "Default")
      (node (ref "J1") (pin "13") (pinfunction "GPIO27/GEN2_13") (pintype "bidirectional"))
    )
    (net (code "135") (name "unconnected-(J1-ID_SC-Pad28)") (class "Default")
      (node (ref "J1") (pin "28") (pinfunction "ID_SC_28") (pintype "bidirectional"))
    )
    (net (code "136") (name "unconnected-(J1-ID_SD-Pad27)") (class "Default")
      (node (ref "J1") (pin "27") (pinfunction "ID_SD_27") (pintype "bidirectional"))
    )
    (net (code "137") (name "unconnected-(J1-~{CE}{slash}GPIO7-Pad26)") (class "Default")
      (node (ref "J1") (pin "26") (pinfunction "~{CE}/GPIO7_26") (pintype "bidirectional"))
    )
    (net (code "138") (name "unconnected-(U1-B_IQ_TX-Pad37)") (class "Default")
      (node (ref "U1") (pin "37") (pinfunction "B_IQ_TX_37") (pintype "bidirectional"))
    )
    (net (code "139") (name "unconnected-(U1-B_QI_TX-Pad38)") (class "Default")
      (node (ref "U1") (pin "38") (pinfunction "B_QI_TX_38") (pintype "bidirectional"))
    )
    (net (code "140") (name "unconnected-(U1-LNA_B_CTRL-Pad27)") (class "Default")
      (node (ref "U1") (pin "27") (pinfunction "LNA_B_CTRL_27") (pintype "bidirectional"))
    )
    (net (code "141") (name "unconnected-(U1-PA_B_CTRL-Pad26)") (class "Default")
      (node (ref "U1") (pin "26") (pinfunction "PA_B_CTRL_26") (pintype "bidirectional"))
    )
    (net (code "142") (name "unconnected-(U1-PA_GAIN[0]-Pad18)") (class "Default")
      (node (ref "U1") (pin "18") (pinfunction "PA_GAIN[0]_18") (pintype "bidirectional"))
    )
    (net (code "143") (name "unconnected-(U1-PA_GAIN[1]-Pad17)") (class "Default")
      (node (ref "U1") (pin "17") (pinfunction "PA_GAIN[1]_17") (pintype "bidirectional"))
    )
    (net (code "144") (name "unconnected-(U1-RADIO_A_EN-Pad13)") (class "Default")
      (node (ref "U1") (pin "13") (pinfunction "RADIO_A_EN_13") (pintype "bidirectional"))
    )
    (net (code "145") (name "unconnected-(U1-RADIO_B_EN-Pad28)") (class "Default")
      (node (ref "U1") (pin "28") (pinfunction "RADIO_B_EN_28") (pintype "bidirectional"))
    )
    (net (code "146") (name "unconnected-(U2-RTCM-Pad14)") (class "Default")
      (node (ref "U2") (pin "14") (pinfunction "RTCM_14") (pintype "bidirectional"))
    )
    (net (code "147") (name "unconnected-(U2-VBACKUP-Pad4)") (class "Default")
      (node (ref "U2") (pin "4") (pinfunction "VBACKUP_4") (pintype "bidirectional"))
    )
    (net (code "148") (name "unconnected-(U5-PGOOD-Pad8)") (class "Default")
      (node (ref "U5") (pin "8") (pinfunction "PGOOD_8") (pintype "bidirectional"))
    )
    (net (code "149") (name "unconnected-(U6-CLK_IN-Pad11)") (class "Default")
      (node (ref "U6") (pin "11") (pinfunction "CLK_IN_11") (pintype "bidirectional"))
    )
    (net (code "150") (name "unconnected-(U6-DIO0-Pad21)") (class "Default")
      (node (ref "U6") (pin "21") (pinfunction "DIO0_21") (pintype "bidirectional"))
    )
    (net (code "151") (name "unconnected-(U6-DIO1-Pad22)") (class "Default")
      (node (ref "U6") (pin "22") (pinfunction "DIO1_22") (pintype "bidirectional"))
    )
    (net (code "152") (name "unconnected-(U6-DIO2-Pad23)") (class "Default")
      (node (ref "U6") (pin "23") (pinfunction "DIO2_23") (pintype "bidirectional"))
    )
    (net (code "153") (name "unconnected-(U6-DIO3-Pad24)") (class "Default")
      (node (ref "U6") (pin "24") (pinfunction "DIO3_24") (pintype "bidirectional"))
    )
    (net (code "154") (name "unconnected-(U6-RF_ON-Pad29)") (class "Default")
      (node (ref "U6") (pin "29") (pinfunction "RF_ON_29") (pintype "bidirectional"))
    )
    (net (code "155") (name "unconnected-(U6-RF_OP-Pad30)") (class "Default")
      (node (ref "U6") (pin "30") (pinfunction "RF_OP_30") (pintype "bidirectional"))
    )
    (net (code "156") (name "unconnected-(U6-XTA-Pad6)") (class "Default")
      (node (ref "U6") (pin "6") (pinfunction "XTA_6") (pintype "bidirectional"))
    )
    (net (code "157") (name "unconnected-(U7-CLK_OUT-Pad10)") (class "Default")
      (node (ref "U7") (pin "10") (pinfunction "CLK_OUT_10") (pintype "bidirectional"))
    )
    (net (code "158") (name "unconnected-(U7-DIO0-Pad21)") (class "Default")
      (node (ref "U7") (pin "21") (pinfunction "DIO0_21") (pintype "bidirectional"))
    )
    (net (code "159") (name "unconnected-(U7-DIO1-Pad22)") (class "Default")
      (node (ref "U7") (pin "22") (pinfunction "DIO1_22") (pintype "bidirectional"))
    )
    (net (code "160") (name "unconnected-(U7-DIO2-Pad23)") (class "Default")
      (node (ref "U7") (pin "23") (pinfunction "DIO2_23") (pintype "bidirectional"))
    )
    (net (code "161") (name "unconnected-(U7-DIO3-Pad24)") (class "Default")
      (node (ref "U7") (pin "24") (pinfunction "DIO3_24") (pintype "bidirectional"))
    )
    (net (code "162") (name "unconnected-(U7-XTA-Pad6)") (class "Default")
      (node (ref "U7") (pin "6") (pinfunction "XTA_6") (pintype "bidirectional"))
    )
    (net (code "163") (name "unconnected-(U10-N{slash}C-Pad22)") (class "Default")
      (node (ref "U10") (pin "22") (pinfunction "N/C_22") (pintype "bidirectional"))
    )
  )
)
